# 06_-_MICRO_CONTROLLER_CONNECTORS.net
KiCad netlist of a schematic drawn in Altium Designer
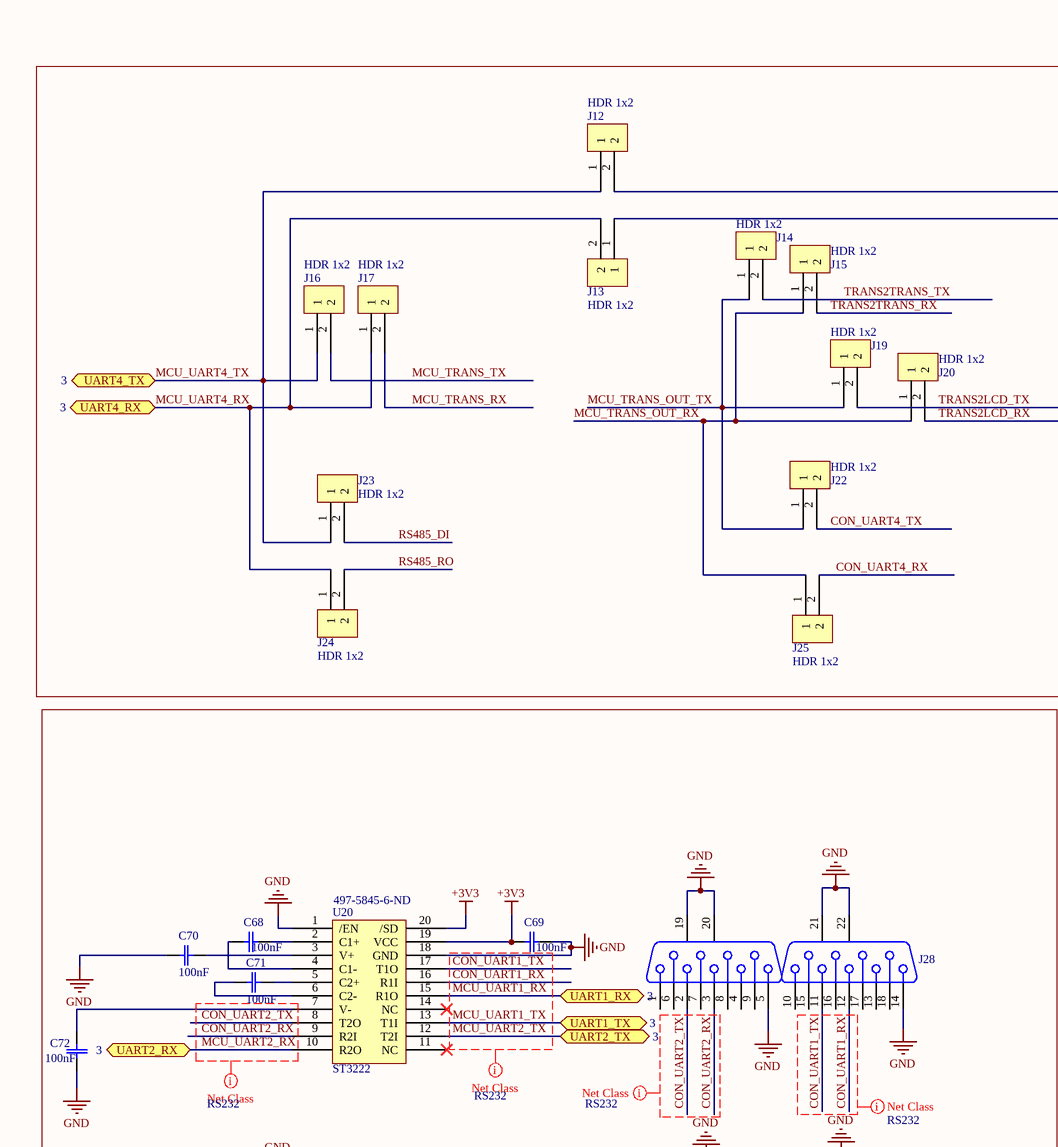
[diagram p0: [06] - MICRO CONTROLLER CONNECTORS.SchDoc, top left]
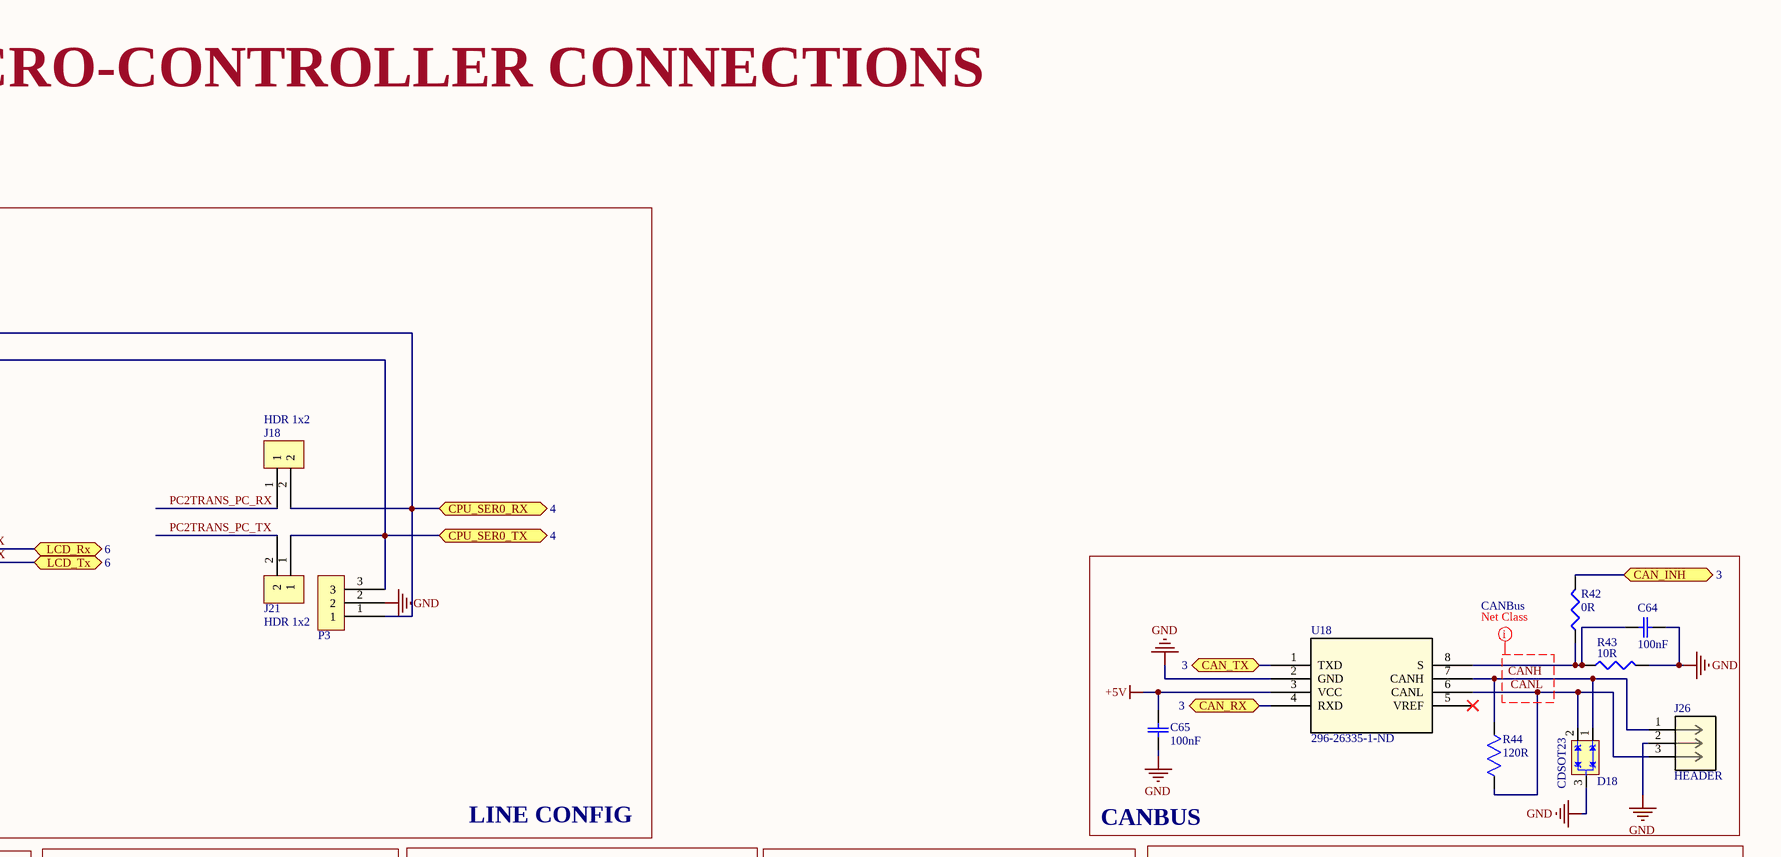
[diagram p1: [06] - MICRO CONTROLLER CONNECTORS.SchDoc, top right]
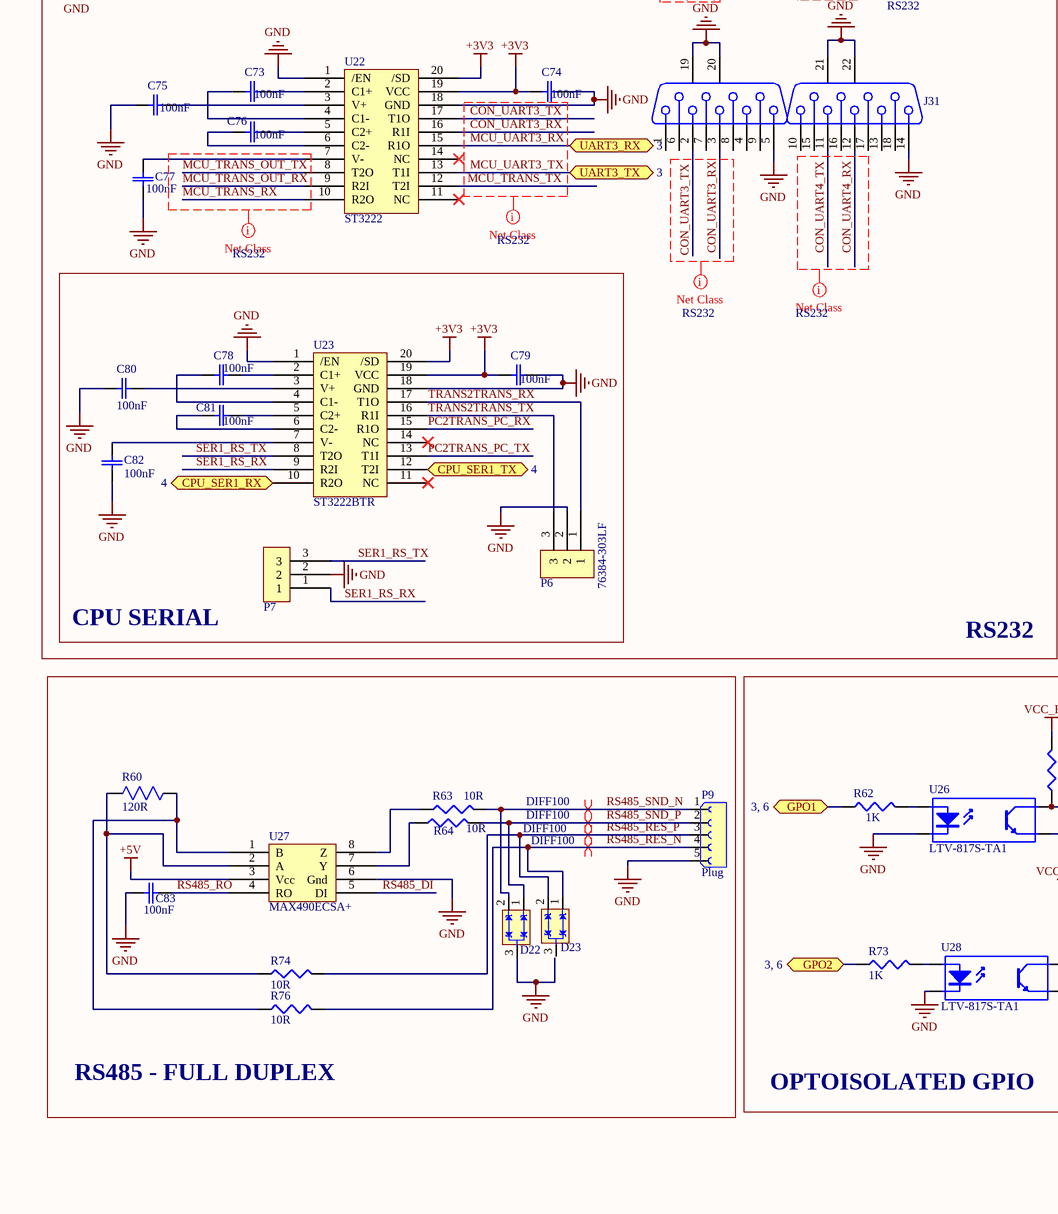
[diagram p2: [06] - MICRO CONTROLLER CONNECTORS.SchDoc, bottom left]
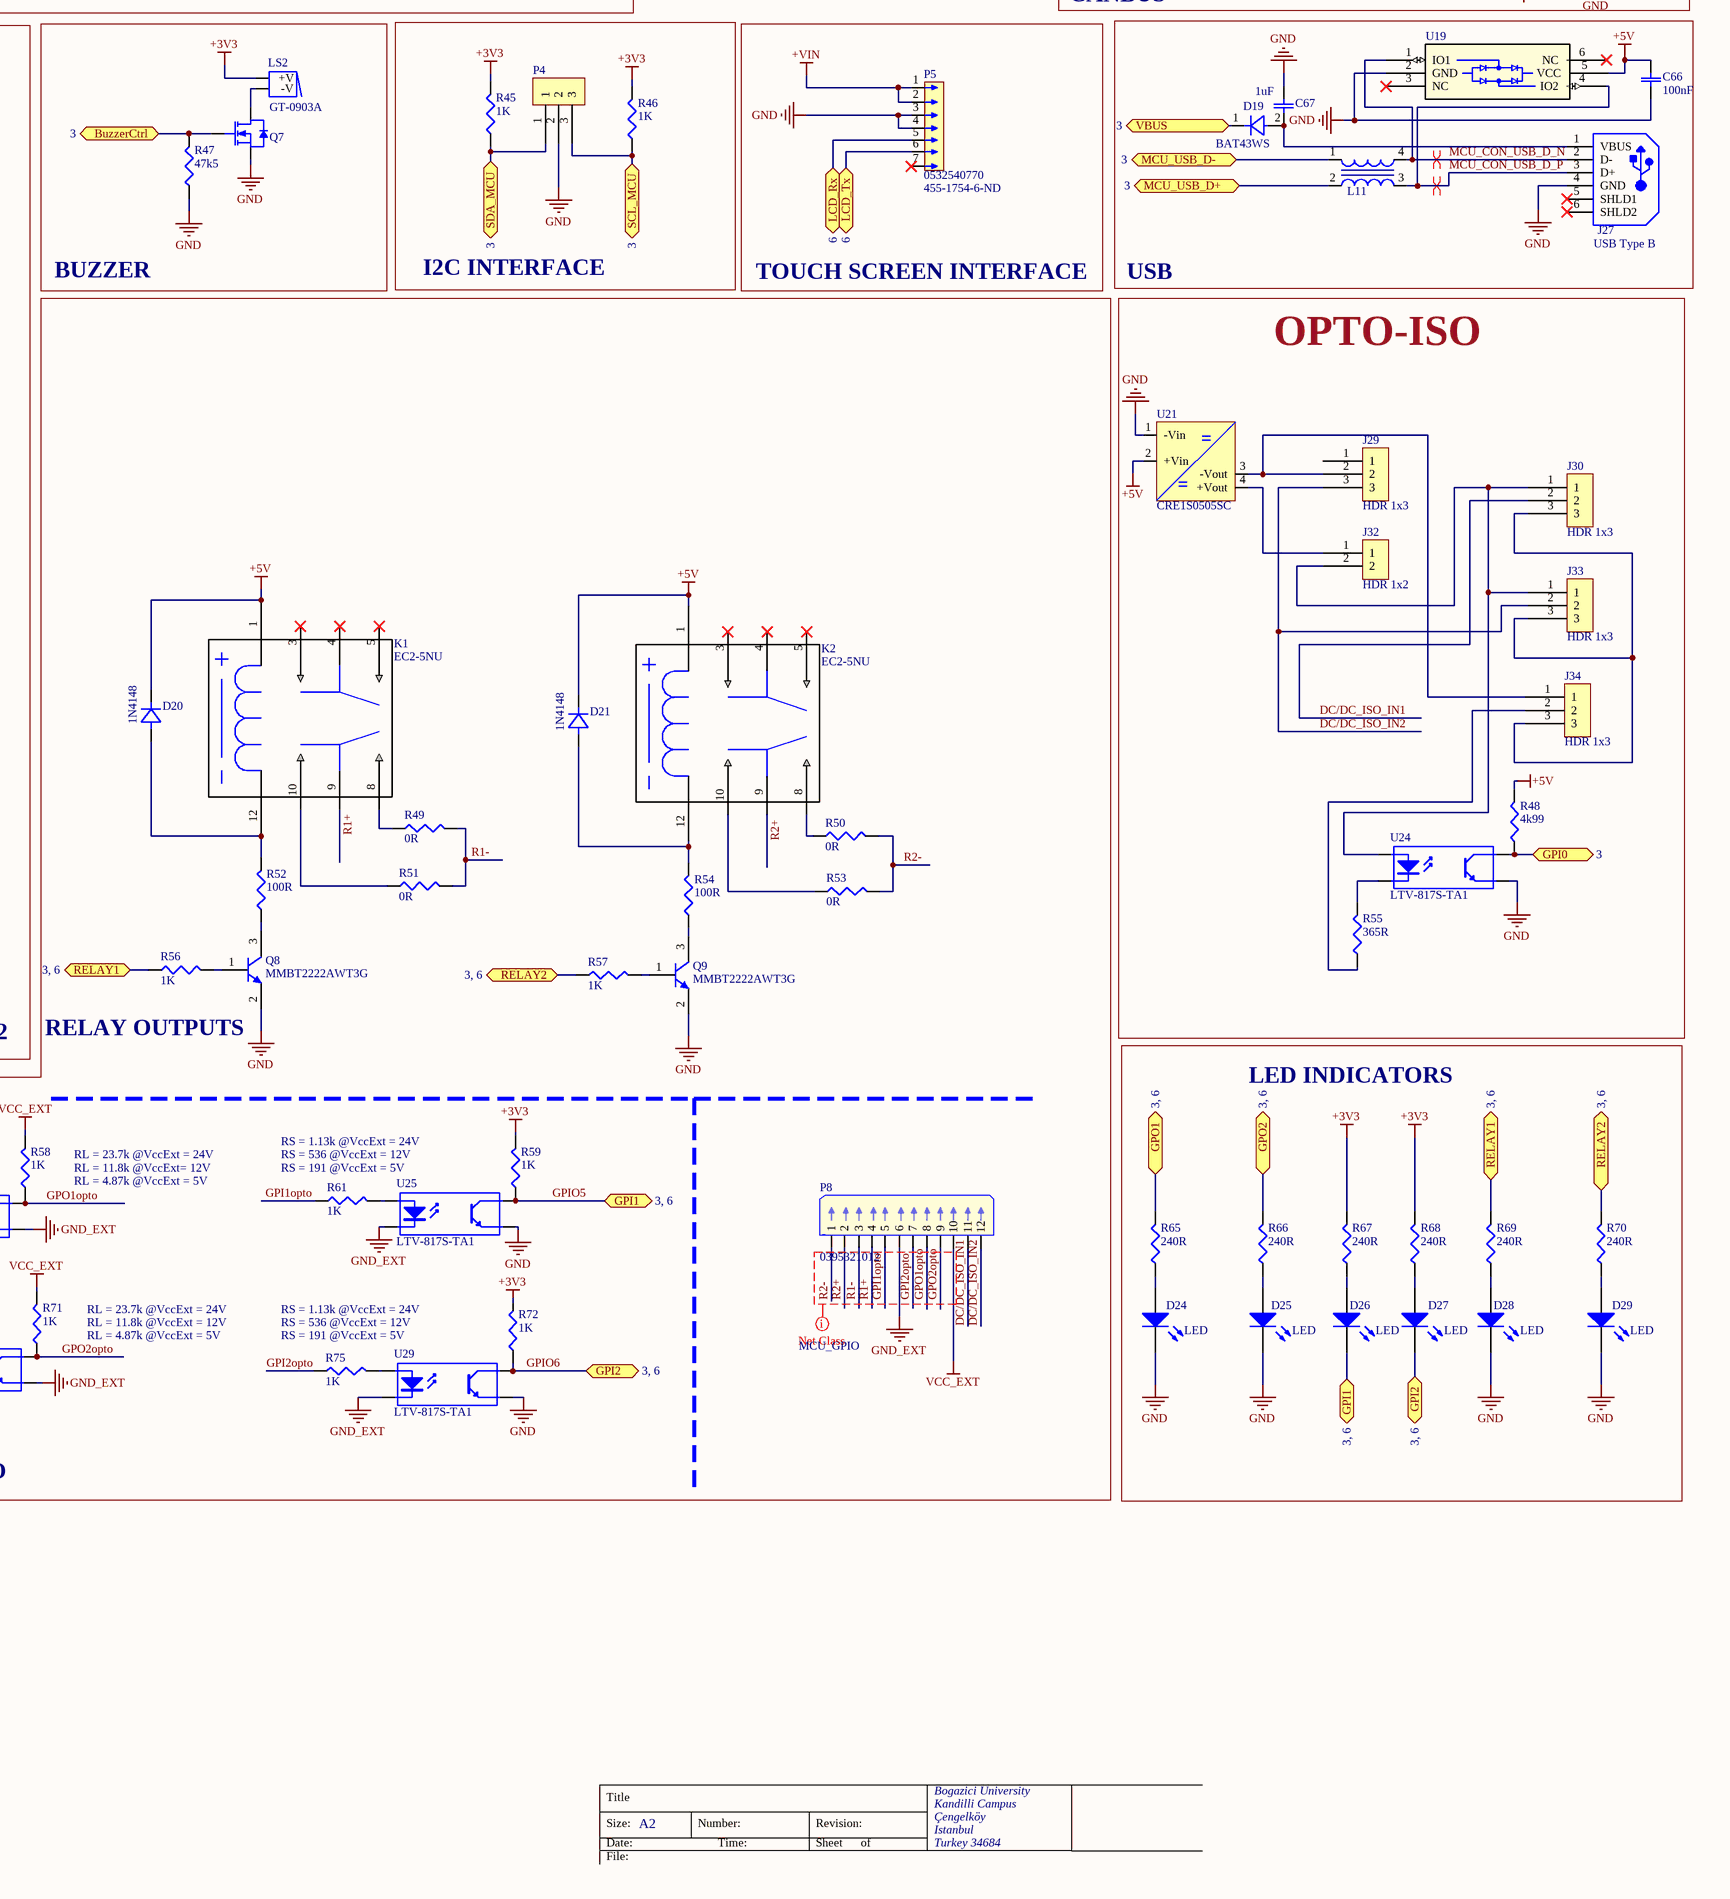
[diagram p3: [06] - MICRO CONTROLLER CONNECTORS.SchDoc, bottom right]

(export (version "E")
  (design (tool "Eeschema 10.0.6"))
  (components
    (comp (ref "C64")
      (value "100nF")
      (footprint "C0402")
      (description "CAP CER 0.1UF 25V X5R 0402")
      (fields (field (name "TOLERANCE") "±10%") (field (name ".CHECKED SCH") "CHK"))
      (libsource (lib "SYNCBOX_V3I1") (part "CL05A104KA5NNNC"))
    )
    (comp (ref "C65")
      (value "100nF")
      (footprint "C0402")
      (description "CAP CER 0.1UF 25V X5R 0402")
      (fields (field (name "TOLERANCE") "±10%"))
      (libsource (lib "SYNCBOX_V3I1") (part "CL05A104KA5NNNC"))
    )
    (comp (ref "C66")
      (value "100nF")
      (footprint "C0402")
      (description "CAP CER 0.1UF 25V X5R 0402")
      (fields (field (name "TOLERANCE") "±10%") (field (name ".CHECKED SCH") "CHK"))
      (libsource (lib "SYNCBOX_V3I1") (part "CL05A104KA5NNNC"))
    )
    (comp (ref "C67")
      (value "1uF")
      (footprint "CAP_3216")
      (description "CAP CER 1UF 50V X8R 1206")
      (fields
        (field (name "MANUFACTURER_PART_NUMBER") "CGA5L3X8R1H105K160AB")
        (field (name "TOLERANCE") "±10%")
        (field (name ".CHECKED SCH") "CHK")
      )
      (libsource (lib "SYNCBOX_V3I1") (part "CGA5L3X8R1H105K1"))
    )
    (comp (ref "C68")
      (value "100nF")
      (footprint "C0402")
      (description "CAP CER 0.1UF 25V X5R 0402")
      (fields (field (name "TOLERANCE") "±10%") (field (name ".CHECKED SCH") "CHK"))
      (libsource (lib "SYNCBOX_V3I1") (part "CL05A104KA5NNNC"))
    )
    (comp (ref "C69")
      (value "100nF")
      (footprint "C0402")
      (description "CAP CER 0.1UF 25V X5R 0402")
      (fields (field (name "TOLERANCE") "±10%") (field (name ".CHECKED SCH") "CHK"))
      (libsource (lib "SYNCBOX_V3I1") (part "CL05A104KA5NNNC"))
    )
    (comp (ref "C70")
      (value "100nF")
      (footprint "C0402")
      (description "CAP CER 0.1UF 25V X5R 0402")
      (fields (field (name "TOLERANCE") "±10%") (field (name ".CHECKED SCH") "CHK"))
      (libsource (lib "SYNCBOX_V3I1") (part "CL05A104KA5NNNC"))
    )
    (comp (ref "C71")
      (value "100nF")
      (footprint "C0402")
      (description "CAP CER 0.1UF 25V X5R 0402")
      (fields (field (name "TOLERANCE") "±10%") (field (name ".CHECKED SCH") "CHK"))
      (libsource (lib "SYNCBOX_V3I1") (part "CL05A104KA5NNNC"))
    )
    (comp (ref "C72")
      (value "100nF")
      (footprint "C0402")
      (description "CAP CER 0.1UF 25V X5R 0402")
      (fields (field (name "TOLERANCE") "±10%") (field (name ".CHECKED SCH") "CHK"))
      (libsource (lib "SYNCBOX_V3I1") (part "CL05A104KA5NNNC"))
    )
    (comp (ref "C73")
      (value "100nF")
      (footprint "C0402")
      (description "CAP CER 0.1UF 25V X5R 0402")
      (fields (field (name "TOLERANCE") "±10%") (field (name ".CHECKED SCH") "CHK"))
      (libsource (lib "SYNCBOX_V3I1") (part "CL05A104KA5NNNC"))
    )
    (comp (ref "C74")
      (value "100nF")
      (footprint "C0402")
      (description "CAP CER 0.1UF 25V X5R 0402")
      (fields (field (name "TOLERANCE") "±10%") (field (name ".CHECKED SCH") "CHK"))
      (libsource (lib "SYNCBOX_V3I1") (part "CL05A104KA5NNNC"))
    )
    (comp (ref "C75")
      (value "100nF")
      (footprint "C0402")
      (description "CAP CER 0.1UF 25V X5R 0402")
      (fields (field (name "TOLERANCE") "±10%") (field (name ".CHECKED SCH") "CHK"))
      (libsource (lib "SYNCBOX_V3I1") (part "CL05A104KA5NNNC"))
    )
    (comp (ref "C76")
      (value "100nF")
      (footprint "C0402")
      (description "CAP CER 0.1UF 25V X5R 0402")
      (fields (field (name "TOLERANCE") "±10%") (field (name ".CHECKED SCH") "CHK"))
      (libsource (lib "SYNCBOX_V3I1") (part "CL05A104KA5NNNC"))
    )
    (comp (ref "C77")
      (value "100nF")
      (footprint "C0402")
      (description "CAP CER 0.1UF 25V X5R 0402")
      (fields (field (name "TOLERANCE") "±10%") (field (name ".CHECKED SCH") "CHK"))
      (libsource (lib "SYNCBOX_V3I1") (part "CL05A104KA5NNNC"))
    )
    (comp (ref "C78")
      (value "100nF")
      (footprint "C0402")
      (description "CAP CER 0.1UF 25V X5R 0402")
      (fields (field (name "TOLERANCE") "±10%") (field (name ".CHECKED SCH") "CHK"))
      (libsource (lib "SYNCBOX_V3I1") (part "CL05A104KA5NNNC"))
    )
    (comp (ref "C79")
      (value "100nF")
      (footprint "C0402")
      (description "CAP CER 0.1UF 25V X5R 0402")
      (fields (field (name "TOLERANCE") "±10%") (field (name ".CHECKED SCH") "CHK"))
      (libsource (lib "SYNCBOX_V3I1") (part "CL05A104KA5NNNC"))
    )
    (comp (ref "C80")
      (value "100nF")
      (footprint "C0402")
      (description "CAP CER 0.1UF 25V X5R 0402")
      (fields (field (name "TOLERANCE") "±10%") (field (name ".CHECKED SCH") "CHK"))
      (libsource (lib "SYNCBOX_V3I1") (part "CL05A104KA5NNNC"))
    )
    (comp (ref "C81")
      (value "100nF")
      (footprint "C0402")
      (description "CAP CER 0.1UF 25V X5R 0402")
      (fields (field (name "TOLERANCE") "±10%") (field (name ".CHECKED SCH") "CHK"))
      (libsource (lib "SYNCBOX_V3I1") (part "CL05A104KA5NNNC"))
    )
    (comp (ref "C82")
      (value "100nF")
      (footprint "C0402")
      (description "CAP CER 0.1UF 25V X5R 0402")
      (fields (field (name "TOLERANCE") "±10%") (field (name ".CHECKED SCH") "CHK"))
      (libsource (lib "SYNCBOX_V3I1") (part "CL05A104KA5NNNC"))
    )
    (comp (ref "C83")
      (value "100nF")
      (footprint "C0402")
      (description "CAP CER 0.1UF 25V X5R 0402")
      (fields (field (name "TOLERANCE") "±10%"))
      (libsource (lib "SYNCBOX_V3I1") (part "CL05A104KA5NNNC"))
    )
    (comp (ref "D18")
      (value "CDSOT23")
      (footprint "SOT-23-3")
      (description "TVS DIODE 24V 40V SOT23")
      (fields (field (name ".CHECKED SCH") "CHK"))
      (libsource (lib "SYNCBOX_V3I1") (part "CDSOT23"))
    )
    (comp (ref "D19")
      (value "BAT43WS")
      (footprint "SOD323")
      (description "DIODE SCHOTTKY 30V 200MA SOD323")
      (fields (field (name ".CHECKED SCH") "CHK"))
      (libsource (lib "SYNCBOX_V3I1") (part "BAT43WS-7-F"))
    )
    (comp (ref "D20")
      (value "1N4148")
      (footprint "SOD123-L")
      (description "DIODE GEN PURP 100V 150MA SOD123")
      (fields
        (field (name "BASE PART NUMBER") "1N4148W")
        (field (name "COPYRIGHT") "Copyright (C) 2016 Accelerated Designs. All rights reserved")
        (field (name ".CHECKED SCH") "CHK")
      )
      (libsource (lib "SYNCBOX_V3I1") (part "1N4148"))
    )
    (comp (ref "D21")
      (value "1N4148")
      (footprint "SOD123-L")
      (description "DIODE GEN PURP 100V 150MA SOD123")
      (fields
        (field (name "BASE PART NUMBER") "1N4148W")
        (field (name "COPYRIGHT") "Copyright (C) 2016 Accelerated Designs. All rights reserved")
        (field (name ".CHECKED SCH") "CHK")
      )
      (libsource (lib "SYNCBOX_V3I1") (part "1N4148"))
    )
    (comp (ref "D22")
      (value "TVS")
      (footprint "SOT-23-3")
      (fields (field (name ".CHECKED SCH") "CHK") (field (name ".CHECKED PCB") "CHK"))
      (libsource (lib "SYNCBOX_V3I1") (part "CDSOT23-SM712"))
    )
    (comp (ref "D23")
      (value "TVS")
      (footprint "SOT-23-3")
      (libsource (lib "SYNCBOX_V3I1") (part "CDSOT23-SM712"))
    )
    (comp (ref "D24")
      (value "LED")
      (footprint "D0603_Directional")
      (description "LED COOL WHITE DIFFUSED 0603 SMD")
      (fields (field (name ".CHECKED SCH") "CHK"))
      (libsource (lib "SYNCBOX_V3I1") (part "LW Q38E-Q1OO-3K6L-1"))
    )
    (comp (ref "D25")
      (value "LED")
      (footprint "D0603_Directional")
      (description "LED COOL WHITE DIFFUSED 0603 SMD")
      (fields (field (name ".CHECKED SCH") "CHK"))
      (libsource (lib "SYNCBOX_V3I1") (part "LW Q38E-Q1OO-3K6L-1"))
    )
    (comp (ref "D26")
      (value "LED")
      (footprint "D0603_Directional")
      (description "LED COOL WHITE DIFFUSED 0603 SMD")
      (fields (field (name ".CHECKED SCH") "CHK"))
      (libsource (lib "SYNCBOX_V3I1") (part "LW Q38E-Q1OO-3K6L-1"))
    )
    (comp (ref "D27")
      (value "LED")
      (footprint "D0603_Directional")
      (description "LED RED DIFFUSED 0603 SMD")
      (fields (field (name "PUBLISHER") "Altium Limited") (field (name ".CHECKED SCH") "CHK"))
      (libsource (lib "SYNCBOX_V3I1") (part "LS Q976-NR-1"))
    )
    (comp (ref "D28")
      (value "LED")
      (footprint "D0603_Directional")
      (description "LED COOL WHITE DIFFUSED 0603 SMD")
      (fields (field (name ".CHECKED SCH") "CHK"))
      (libsource (lib "SYNCBOX_V3I1") (part "LW Q38E-Q1OO-3K6L-1"))
    )
    (comp (ref "D29")
      (value "LED")
      (footprint "D0603_Directional")
      (description "LED COOL WHITE DIFFUSED 0603 SMD")
      (fields (field (name ".CHECKED SCH") "CHK"))
      (libsource (lib "SYNCBOX_V3I1") (part "LW Q38E-Q1OO-3K6L-1"))
    )
    (comp (ref "J12")
      (value "HDR 1x2")
      (footprint "HDR_1x2_2.54MM")
      (description "BERGSTIK II .100\" SR STRAIGHT")
      (fields
        (field (name "MANUFACTURER") "FCI")
        (field (name "MANUFACTURER PART NUMBER") "68001-202HLF")
        (field (name ".CHECKED SCH") "CHK")
      )
      (libsource (lib "") (part "68001-202HLF_1"))
    )
    (comp (ref "J13")
      (value "HDR 1x2")
      (footprint "HDR_1x2_2.54MM")
      (description "BERGSTIK II .100\" SR STRAIGHT")
      (fields
        (field (name "MANUFACTURER") "FCI")
        (field (name "MANUFACTURER PART NUMBER") "68001-202HLF")
        (field (name ".CHECKED SCH") "CHK")
      )
      (libsource (lib "iMX6 Rex Development Baseboard V1I1") (part "68001-202HLF"))
    )
    (comp (ref "J14")
      (value "HDR 1x2")
      (footprint "HDR_1x2_2.54MM")
      (description "BERGSTIK II .100\" SR STRAIGHT")
      (fields
        (field (name "MANUFACTURER") "FCI")
        (field (name "MANUFACTURER PART NUMBER") "68001-202HLF")
        (field (name ".CHECKED SCH") "CHK")
      )
      (libsource (lib "") (part "68001-202HLF_1"))
    )
    (comp (ref "J15")
      (value "HDR 1x2")
      (footprint "HDR_1x2_2.54MM")
      (description "BERGSTIK II .100\" SR STRAIGHT")
      (fields
        (field (name "MANUFACTURER") "FCI")
        (field (name "MANUFACTURER PART NUMBER") "68001-202HLF")
        (field (name ".CHECKED SCH") "CHK")
      )
      (libsource (lib "") (part "68001-202HLF_1"))
    )
    (comp (ref "J16")
      (value "HDR 1x2")
      (footprint "HDR_1x2_2.54MM")
      (description "BERGSTIK II .100\" SR STRAIGHT")
      (fields
        (field (name "MANUFACTURER") "FCI")
        (field (name "MANUFACTURER PART NUMBER") "68001-202HLF")
        (field (name ".CHECKED SCH") "CHK")
      )
      (libsource (lib "") (part "68001-202HLF_1"))
    )
    (comp (ref "J17")
      (value "HDR 1x2")
      (footprint "HDR_1x2_2.54MM")
      (description "BERGSTIK II .100\" SR STRAIGHT")
      (fields
        (field (name "MANUFACTURER") "FCI")
        (field (name "MANUFACTURER PART NUMBER") "68001-202HLF")
        (field (name ".CHECKED SCH") "CHK")
      )
      (libsource (lib "") (part "68001-202HLF_1"))
    )
    (comp (ref "J18")
      (value "HDR 1x2")
      (footprint "HDR_1x2_2.54MM")
      (description "BERGSTIK II .100\" SR STRAIGHT")
      (fields (field (name "MANUFACTURER") "FCI") (field (name "MANUFACTURER PART NUMBER") "68001-202HLF"))
      (libsource (lib "") (part "68001-202HLF_1"))
    )
    (comp (ref "J19")
      (value "HDR 1x2")
      (footprint "HDR_1x2_2.54MM")
      (description "BERGSTIK II .100\" SR STRAIGHT")
      (fields
        (field (name "MANUFACTURER") "FCI")
        (field (name "MANUFACTURER PART NUMBER") "68001-202HLF")
        (field (name ".CHECKED SCH") "CHK")
      )
      (libsource (lib "") (part "68001-202HLF_1"))
    )
    (comp (ref "J20")
      (value "HDR 1x2")
      (footprint "HDR_1x2_2.54MM")
      (description "BERGSTIK II .100\" SR STRAIGHT")
      (fields
        (field (name "MANUFACTURER") "FCI")
        (field (name "MANUFACTURER PART NUMBER") "68001-202HLF")
        (field (name ".CHECKED SCH") "CHK")
      )
      (libsource (lib "") (part "68001-202HLF_1"))
    )
    (comp (ref "J21")
      (value "HDR 1x2")
      (footprint "HDR_1x2_2.54MM")
      (description "BERGSTIK II .100\" SR STRAIGHT")
      (fields (field (name "MANUFACTURER") "FCI") (field (name "MANUFACTURER PART NUMBER") "68001-202HLF"))
      (libsource (lib "iMX6 Rex Development Baseboard V1I1") (part "68001-202HLF"))
    )
    (comp (ref "J22")
      (value "HDR 1x2")
      (footprint "HDR_1x2_2.54MM")
      (description "BERGSTIK II .100\" SR STRAIGHT")
      (fields
        (field (name "MANUFACTURER") "FCI")
        (field (name "MANUFACTURER PART NUMBER") "68001-202HLF")
        (field (name ".CHECKED SCH") "CHK")
      )
      (libsource (lib "") (part "68001-202HLF_1"))
    )
    (comp (ref "J23")
      (value "HDR 1x2")
      (footprint "HDR_1x2_2.54MM")
      (description "BERGSTIK II .100\" SR STRAIGHT")
      (fields
        (field (name "MANUFACTURER") "FCI")
        (field (name "MANUFACTURER PART NUMBER") "68001-202HLF")
        (field (name ".CHECKED SCH") "CHK")
      )
      (libsource (lib "") (part "68001-202HLF_1"))
    )
    (comp (ref "J24")
      (value "HDR 1x2")
      (footprint "HDR_1x2_2.54MM")
      (description "BERGSTIK II .100\" SR STRAIGHT")
      (fields
        (field (name "MANUFACTURER") "FCI")
        (field (name "MANUFACTURER PART NUMBER") "68001-202HLF")
        (field (name ".CHECKED SCH") "CHK")
      )
      (libsource (lib "") (part "68001-202HLF_2"))
    )
    (comp (ref "J25")
      (value "HDR 1x2")
      (footprint "HDR_1x2_2.54MM")
      (description "BERGSTIK II .100\" SR STRAIGHT")
      (fields
        (field (name "MANUFACTURER") "FCI")
        (field (name "MANUFACTURER PART NUMBER") "68001-202HLF")
        (field (name ".CHECKED SCH") "CHK")
      )
      (libsource (lib "") (part "68001-202HLF_2"))
    )
    (comp (ref "J26")
      (value "HEADER")
      (footprint "TerminalBlock3P508")
      (description "TERM BLOCK HDR 3POS 90DEG 5MM")
      (fields (field (name "MANUFACTURER_PART_NUMBER") "796644-3"))
      (libsource (lib "SYNCBOX_V3I1") (part "796644-3"))
    )
    (comp (ref "J27")
      (value "USB Type B")
      (footprint "USB-B RECEPTACLE")
      (fields (field (name ".CHECKED SCH") "CHK"))
      (libsource (lib "TE Audio, Video and High Speed Serial Connectors") (part "292304-1"))
    )
    (comp (ref "J28")
      (value "DSUB-9 Stacked")
      (footprint "DSUB9-Double")
      (description "189-009-613R491")
      (fields (field (name "PUBLISHER") "Altium Limited") (field (name ".CHECKED SCH") "CHK"))
      (libsource (lib "SYNCBOX_V3I1") (part "DSUB-9 Stack"))
    )
    (comp (ref "J29")
      (value "HDR 1x3")
      (footprint "HDR_1X3_2.54MM")
      (description "BERGSTIK II .100\" SR STRAIGHT")
      (fields
        (field (name "MANUFACTURER") "FCI")
        (field (name "MANUFACTURER PART NUMBER") "68000-103HLF")
        (field (name ".CHECKED SCH") "CHK")
        (field (name ".CREATOR") "MM")
      )
      (libsource (lib "SYNCBOX_V3I1") (part "68000-103HLF"))
    )
    (comp (ref "J30")
      (value "HDR 1x3")
      (footprint "Hdr_1x3_2.54mm")
      (description "BERGSTIK II .100\" SR STRAIGHT")
      (fields
        (field (name "MANUFACTURER") "FCI")
        (field (name "MANUFACTURER PART NUMBER") "68000-103HLF")
        (field (name ".CREATOR") "MM")
        (field (name ".CHECKED SCH") "CHK")
      )
      (libsource (lib "iMX6 Rex Development Baseboard V1I1") (part "68000-103HLF"))
    )
    (comp (ref "J31")
      (value "DSUB-9 Stacked")
      (footprint "DSUB9-Double")
      (description "189-009-613R491")
      (fields (field (name "PUBLISHER") "Altium Limited") (field (name ".CHECKED SCH") "CHK"))
      (libsource (lib "SYNCBOX_V3I1") (part "DSUB-9 Stack"))
    )
    (comp (ref "J32")
      (value "HDR 1x2")
      (footprint "HDR_1x2_2.54MM")
      (description "BERGSTIK II .100\" SR STRAIGHT")
      (fields
        (field (name "MANUFACTURER") "FCI")
        (field (name "MANUFACTURER PART NUMBER") "68001-202HLF")
        (field (name ".CHECKED SCH") "CHK")
      )
      (libsource (lib "") (part "68001-202HLF_3"))
    )
    (comp (ref "J33")
      (value "HDR 1x3")
      (footprint "Hdr_1x3_2.54mm")
      (description "BERGSTIK II .100\" SR STRAIGHT")
      (fields
        (field (name "MANUFACTURER") "FCI")
        (field (name "MANUFACTURER PART NUMBER") "68000-103HLF")
        (field (name ".CREATOR") "MM")
        (field (name ".CHECKED SCH") "CHK")
      )
      (libsource (lib "iMX6 Rex Development Baseboard V1I1") (part "68000-103HLF"))
    )
    (comp (ref "J34")
      (value "HDR 1x3")
      (footprint "Hdr_1x3_2.54mm")
      (description "BERGSTIK II .100\" SR STRAIGHT")
      (fields
        (field (name "MANUFACTURER") "FCI")
        (field (name "MANUFACTURER PART NUMBER") "68000-103HLF")
        (field (name ".CREATOR") "MM")
        (field (name ".CHECKED SCH") "CHK")
      )
      (libsource (lib "iMX6 Rex Development Baseboard V1I1") (part "68000-103HLF"))
    )
    (comp (ref "K1")
      (value "EC2-5NU")
      (footprint "EC2NU")
      (description "RELAY GEN PURPOSE DPDT 2A 5V")
      (fields (field (name ".CHECKED SCH") "CHK"))
      (libsource (lib "SYNCBOX_V3I1") (part "EC2-5NU"))
    )
    (comp (ref "K2")
      (value "EC2-5NU")
      (footprint "EC2NU")
      (description "RELAY GEN PURPOSE DPDT 2A 5V")
      (libsource (lib "SYNCBOX_V3I1") (part "EC2-5NU"))
    )
    (comp (ref "L11")
      (value "ACM2012-900-2P-T002")
      (footprint "ACM2012")
      (description "CHOKE COMM MODE 90 OHM .4A SMD")
      (fields
        (field (name "MANUFACTURER") "TDK Corporation")
        (field (name "TOLERANCE") "±1%")
        (field (name ".CHECKED PCB") "CHK")
        (field (name ".CHECKED SCH") "CHK")
      )
      (libsource (lib "SYNCBOX_V3I1") (part "ACM2012-900-2P-T002"))
    )
    (comp (ref "LS2")
      (value "GT-0903A")
      (footprint "GT-0903A")
      (description "AUDIO MAGNETIC XDCR 2-4V TH")
      (fields (field (name ".CHECKED PCB") "CHK") (field (name ".CHECKED SCH") "CHK"))
      (libsource (lib "SYNCBOX_V3I1") (part "GT-0903A"))
    )
    (comp (ref "P3")
      (value "76384-303LF")
      (footprint "HDR_1x3_2.54MM_SHDR_V2")
      (description "CONN HEADER 3POS .100\" STR GOLD")
      (fields (field (name "MANUFACTURER") "FCI") (field (name ".CREATOR") "MM"))
      (libsource (lib "") (part "76384-303LF_1"))
    )
    (comp (ref "P4")
      (value "76384-303LF")
      (footprint "HDR_1x3_2.54MM_SHDR_V2")
      (description "CONN HEADER 3POS .100\" STR GOLD")
      (fields
        (field (name "MANUFACTURER") "FCI")
        (field (name ".CREATOR") "MM")
        (field (name ".CHECKED SCH") "CHK")
      )
      (libsource (lib "SYNCBOX_V3I1") (part "76384-303LF"))
    )
    (comp (ref "P5")
      (value "0532540770")
      (footprint "WM3412-ND")
      (description "HEADER 2MM WTB R/A SQ PIN 7CKT")
      (fields (field (name "SUPPLIER PART NUMBER 1") "455-1754-6-ND"))
      (libsource (lib "SYNCBOX_V3I1") (part "0532540770"))
    )
    (comp (ref "P6")
      (value "76384-303LF")
      (footprint "HDR_1X3_2.54MM_SHDR_V2")
      (description "CONN HEADER 3POS .100\" STR GOLD")
      (fields (field (name "MANUFACTURER") "FCI") (field (name ".CREATOR") "MM"))
      (libsource (lib "") (part "76384-303LF_2"))
    )
    (comp (ref "P7")
      (value "76384-303LF")
      (footprint "HDR_1x3_2.54MM_SHDR_V2")
      (description "CONN HEADER 3POS .100\" STR GOLD")
      (fields
        (field (name "MANUFACTURER") "FCI")
        (field (name ".CREATOR") "MM")
        (field (name ".CHECKED SCH") "CHK")
      )
      (libsource (lib "") (part "76384-303LF_1"))
    )
    (comp (ref "P8")
      (value "0395321012")
      (footprint "WM7852-ND")
      (description "TERM BLOCK HDR 12POS 5.08MM")
      (fields (field (name ".CHECKED SCH") "CHK"))
      (libsource (lib "SYNCBOX_V3I1") (part "0395321012"))
    )
    (comp (ref "P9")
      (value "Plug")
      (footprint "691313710005")
      (description "TERM BLOCK HDR 5POS 90DEG 5MM")
      (fields (field (name ".CHECKED SCH") "CHK"))
      (libsource (lib "SYNCBOX_V3I1") (part "691313710005"))
    )
    (comp (ref "Q7")
      (value "MOSFET N-CH 20V 1A SOT323")
      (footprint "SC70_SOT323")
      (fields (field (name "PUBLISHER") "Altium Limited") (field (name ".CHECKED SCH") "CHK"))
      (libsource (lib "SYNCBOX_V3I1") (part "DMG1012UW-7"))
    )
    (comp (ref "Q8")
      (value "MMBT2222AWT3G")
      (footprint "SC70_SOT323")
      (description "TRANS NPN 40V 0.6A SC70-3")
      (fields
        (field (name "BASE PART NUMBER") "MMBT2222A")
        (field (name ".CHECKED PCB") "CHK")
        (field (name ".CHECKED SCH") "CHK")
      )
      (libsource (lib "SYNCBOX_V3I1") (part "MMBT2222AWT3G"))
    )
    (comp (ref "Q9")
      (value "MMBT2222AWT3G")
      (footprint "SC70_SOT323")
      (description "TRANS NPN 40V 0.6A SC70-3")
      (fields (field (name "BASE PART NUMBER") "MMBT2222A") (field (name ".CHECKED SCH") "CHK"))
      (libsource (lib "SYNCBOX_V3I1") (part "MMBT2222AWT3G"))
    )
    (comp (ref "R42")
      (value "0R")
      (footprint "R0402")
      (description "RES SMD 0 OHM JUMPER 1/16W 0402")
      (fields (field (name "TOLERANCE") "Jumper") (field (name ".CHECKED SCH") "CHK"))
      (libsource (lib "SYNCBOX_V3I1") (part "RC1005J000CS"))
    )
    (comp (ref "R43")
      (value "10R")
      (footprint "R0402")
      (description "RES 10.0 OHM 1/16W 1% 0402 SMD")
      (fields
        (field (name "MANUFACTURER") "Yageo")
        (field (name "MANUFACTURER PART NUMBER") "RC0402FR-0710RL")
        (field (name ".CHECKED SCH") "CHK")
      )
      (libsource (lib "SYNCBOX_V3I1") (part "RC0402FR-0710RL"))
    )
    (comp (ref "R44")
      (value "120R")
      (footprint "RES_R1632")
      (description "RES SMD 120 OHM 3/4W 1206 WIDE")
      (fields (field (name "TOLERANCE") "±1%") (field (name ".CHECKED SCH") "CHK"))
      (libsource (lib "SYNCBOX_V3I1") (part "LTR18EZPF1200"))
    )
    (comp (ref "R45")
      (value "1K")
      (footprint "R0402")
      (description "RES SMD 1K OHM 1% 1/10W 0402")
      (fields (field (name "TOLERANCE") "±1%") (field (name ".CHECKED SCH") "CHK"))
      (libsource (lib "SYNCBOX_V3I1") (part "ERJ-2RKF1001X"))
    )
    (comp (ref "R46")
      (value "1K")
      (footprint "R0402")
      (description "RES SMD 1K OHM 1% 1/10W 0402")
      (fields (field (name "TOLERANCE") "±1%") (field (name ".CHECKED SCH") "CHK"))
      (libsource (lib "SYNCBOX_V3I1") (part "ERJ-2RKF1001X"))
    )
    (comp (ref "R47")
      (value "47k5")
      (footprint "R0402")
      (description "RES 47.5K OHM 1/16W 1% 0402 SMD")
      (fields
        (field (name "MANUFACTURER") "Yageo")
        (field (name "MANUFACTURER PART NUMBER") "RC0402FR-0747K5L")
        (field (name ".CHECKED SCH") "CHK")
      )
      (libsource (lib "SYNCBOX_V3I1") (part "RC0402FR-0747K5L"))
    )
    (comp (ref "R48")
      (value "4k99")
      (footprint "R0402")
      (description "RES TF 4.99K OHM 1% 1/16W 0402")
      (fields
        (field (name "MANUFACTURER") "Stackpole Electronics Inc")
        (field (name "MANUFACTURER PART NUMBER") "RMCF0402FT4K99")
        (field (name ".CHECKED SCH") "CHK")
      )
      (libsource (lib "SYNCBOX_V3I1") (part "RMCF0402FT4K99"))
    )
    (comp (ref "R49")
      (value "0R")
      (footprint "R0402")
      (description "RES SMD 0 OHM JUMPER 1/16W 0402")
      (fields (field (name "TOLERANCE") "Jumper") (field (name ".CHECKED SCH") "CHK"))
      (libsource (lib "SYNCBOX_V3I1") (part "RC1005J000CS"))
    )
    (comp (ref "R50")
      (value "0R")
      (footprint "R0402")
      (description "RES SMD 0 OHM JUMPER 1/16W 0402")
      (fields (field (name "TOLERANCE") "Jumper") (field (name ".CHECKED SCH") "CHK"))
      (libsource (lib "SYNCBOX_V3I1") (part "RC1005J000CS"))
    )
    (comp (ref "R51")
      (value "0R")
      (footprint "R0402")
      (description "RES SMD 0 OHM JUMPER 1/16W 0402")
      (fields (field (name "TOLERANCE") "Jumper") (field (name ".CHECKED SCH") "CHK"))
      (libsource (lib "SYNCBOX_V3I1") (part "RC1005J000CS"))
    )
    (comp (ref "R52")
      (value "100R")
      (footprint "R0402")
      (description "RES SMD 100 OHM 1% 1/16W 0402")
      (fields (field (name "TOLERANCE") "±1%") (field (name ".CHECKED SCH") "CHK"))
      (libsource (lib "SYNCBOX_V3I1") (part "RC1005F101CS"))
    )
    (comp (ref "R53")
      (value "0R")
      (footprint "R0402")
      (description "RES SMD 0 OHM JUMPER 1/16W 0402")
      (fields (field (name "TOLERANCE") "Jumper") (field (name ".CHECKED SCH") "CHK"))
      (libsource (lib "SYNCBOX_V3I1") (part "RC1005J000CS"))
    )
    (comp (ref "R54")
      (value "100R")
      (footprint "R0402")
      (description "RES SMD 100 OHM 1% 1/16W 0402")
      (fields (field (name "TOLERANCE") "±1%") (field (name ".CHECKED SCH") "CHK"))
      (libsource (lib "SYNCBOX_V3I1") (part "RC1005F101CS"))
    )
    (comp (ref "R55")
      (value "365R")
      (footprint "R0402")
      (description "RES TF 365 OHM 1% 1/16W 0402")
      (fields
        (field (name "MANUFACTURER") "Stackpole Electronics Inc")
        (field (name "MANUFACTURER PART NUMBER") "RMCF0402FT365R")
        (field (name ".CHECKED SCH") "CHK")
      )
      (libsource (lib "SYNCBOX_V3I1") (part "RMCF0402FT365R"))
    )
    (comp (ref "R56")
      (value "1K")
      (footprint "R0402")
      (description "RES SMD 1K OHM 1% 1/10W 0402")
      (fields (field (name "TOLERANCE") "±1%") (field (name ".CHECKED SCH") "CHK"))
      (libsource (lib "SYNCBOX_V3I1") (part "ERJ-2RKF1001X"))
    )
    (comp (ref "R57")
      (value "1K")
      (footprint "R0402")
      (description "RES SMD 1K OHM 1% 1/10W 0402")
      (fields (field (name "TOLERANCE") "±1%") (field (name ".CHECKED SCH") "CHK"))
      (libsource (lib "SYNCBOX_V3I1") (part "ERJ-2RKF1001X"))
    )
    (comp (ref "R58")
      (value "1K")
      (footprint "R0402")
      (description "RES SMD 1K OHM 1% 1/10W 0402")
      (fields (field (name "TOLERANCE") "±1%") (field (name ".CHECKED SCH") "CHK"))
      (libsource (lib "SYNCBOX_V3I1") (part "ERJ-2RKF1001X"))
    )
    (comp (ref "R59")
      (value "1K")
      (footprint "R0402")
      (description "RES SMD 1K OHM 1% 1/10W 0402")
      (fields (field (name "TOLERANCE") "±1%"))
      (libsource (lib "SYNCBOX_V3I1") (part "ERJ-2RKF1001X"))
    )
    (comp (ref "R60")
      (value "120R")
      (footprint "RES_R1632")
      (description "RES SMD 120 OHM 3/4W 1206 WIDE")
      (fields (field (name "TOLERANCE") "±1%") (field (name ".CHECKED SCH") "CHK"))
      (libsource (lib "SYNCBOX_V3I1") (part "LTR18EZPF1200"))
    )
    (comp (ref "R61")
      (value "1K")
      (footprint "R0402")
      (description "RES SMD 1K OHM 1% 1/10W 0402")
      (fields (field (name "TOLERANCE") "±1%"))
      (libsource (lib "SYNCBOX_V3I1") (part "ERJ-2RKF1001X"))
    )
    (comp (ref "R62")
      (value "1K")
      (footprint "R0402")
      (description "RES SMD 1K OHM 1% 1/10W 0402")
      (fields (field (name "TOLERANCE") "±1%"))
      (libsource (lib "SYNCBOX_V3I1") (part "ERJ-2RKF1001X"))
    )
    (comp (ref "R63")
      (value "10R")
      (footprint "R0402")
      (description "RES 10.0 OHM 1/16W 1% 0402 SMD")
      (fields
        (field (name "MANUFACTURER") "Yageo")
        (field (name "MANUFACTURER PART NUMBER") "RC0402FR-0710RL")
        (field (name ".CHECKED SCH") "CHK")
      )
      (libsource (lib "SYNCBOX_V3I1") (part "RC0402FR-0710RL"))
    )
    (comp (ref "R64")
      (value "10R")
      (footprint "R0402")
      (description "RES 10.0 OHM 1/16W 1% 0402 SMD")
      (fields
        (field (name "MANUFACTURER") "Yageo")
        (field (name "MANUFACTURER PART NUMBER") "RC0402FR-0710RL")
        (field (name ".CHECKED SCH") "CHK")
      )
      (libsource (lib "SYNCBOX_V3I1") (part "RC0402FR-0710RL"))
    )
    (comp (ref "R65")
      (value "240R")
      (footprint "R0402")
      (description "RES TF 240 OHM 1% 0.0625W 0402")
      (fields
        (field (name "MANUFACTURER") "Stackpole Electronics Inc")
        (field (name "MANUFACTURER PART NUMBER") "RMCF0402FT240R")
        (field (name ".CHECKED SCH") "CHK")
      )
      (libsource (lib "SYNCBOX_V3I1") (part "RMCF0402FT240R"))
    )
    (comp (ref "R66")
      (value "240R")
      (footprint "R0402")
      (description "RES TF 240 OHM 1% 0.0625W 0402")
      (fields
        (field (name "MANUFACTURER") "Stackpole Electronics Inc")
        (field (name "MANUFACTURER PART NUMBER") "RMCF0402FT240R")
        (field (name ".CHECKED SCH") "CHK")
      )
      (libsource (lib "SYNCBOX_V3I1") (part "RMCF0402FT240R"))
    )
    (comp (ref "R67")
      (value "240R")
      (footprint "R0402")
      (description "RES TF 240 OHM 1% 0.0625W 0402")
      (fields
        (field (name "MANUFACTURER") "Stackpole Electronics Inc")
        (field (name "MANUFACTURER PART NUMBER") "RMCF0402FT240R")
        (field (name ".CHECKED SCH") "CHK")
      )
      (libsource (lib "SYNCBOX_V3I1") (part "RMCF0402FT240R"))
    )
    (comp (ref "R68")
      (value "240R")
      (footprint "R0402")
      (description "RES TF 240 OHM 1% 0.0625W 0402")
      (fields
        (field (name "MANUFACTURER") "Stackpole Electronics Inc")
        (field (name "MANUFACTURER PART NUMBER") "RMCF0402FT240R")
        (field (name ".CHECKED SCH") "CHK")
      )
      (libsource (lib "SYNCBOX_V3I1") (part "RMCF0402FT240R"))
    )
    (comp (ref "R69")
      (value "240R")
      (footprint "R0402")
      (description "RES TF 240 OHM 1% 0.0625W 0402")
      (fields
        (field (name "MANUFACTURER") "Stackpole Electronics Inc")
        (field (name "MANUFACTURER PART NUMBER") "RMCF0402FT240R")
        (field (name ".CHECKED SCH") "CHK")
      )
      (libsource (lib "SYNCBOX_V3I1") (part "RMCF0402FT240R"))
    )
    (comp (ref "R70")
      (value "240R")
      (footprint "R0402")
      (description "RES TF 240 OHM 1% 0.0625W 0402")
      (fields
        (field (name "MANUFACTURER") "Stackpole Electronics Inc")
        (field (name "MANUFACTURER PART NUMBER") "RMCF0402FT240R")
        (field (name ".CHECKED SCH") "CHK")
      )
      (libsource (lib "SYNCBOX_V3I1") (part "RMCF0402FT240R"))
    )
    (comp (ref "R71")
      (value "1K")
      (footprint "R0402")
      (description "RES SMD 1K OHM 1% 1/10W 0402")
      (fields (field (name "TOLERANCE") "±1%"))
      (libsource (lib "SYNCBOX_V3I1") (part "ERJ-2RKF1001X"))
    )
    (comp (ref "R72")
      (value "1K")
      (footprint "R0402")
      (description "RES SMD 1K OHM 1% 1/10W 0402")
      (fields (field (name "TOLERANCE") "±1%"))
      (libsource (lib "SYNCBOX_V3I1") (part "ERJ-2RKF1001X"))
    )
    (comp (ref "R73")
      (value "1K")
      (footprint "R0402")
      (description "RES SMD 1K OHM 1% 1/10W 0402")
      (fields (field (name "TOLERANCE") "±1%"))
      (libsource (lib "SYNCBOX_V3I1") (part "ERJ-2RKF1001X"))
    )
    (comp (ref "R74")
      (value "10R")
      (footprint "R0402")
      (description "RES 10.0 OHM 1/16W 1% 0402 SMD")
      (fields
        (field (name "MANUFACTURER") "Yageo")
        (field (name "MANUFACTURER PART NUMBER") "RC0402FR-0710RL")
        (field (name ".CHECKED SCH") "CHK")
      )
      (libsource (lib "SYNCBOX_V3I1") (part "RC0402FR-0710RL"))
    )
    (comp (ref "R75")
      (value "1K")
      (footprint "R0402")
      (description "RES SMD 1K OHM 1% 1/10W 0402")
      (fields (field (name "TOLERANCE") "±1%"))
      (libsource (lib "SYNCBOX_V3I1") (part "ERJ-2RKF1001X"))
    )
    (comp (ref "R76")
      (value "10R")
      (footprint "R0402")
      (description "RES 10.0 OHM 1/16W 1% 0402 SMD")
      (fields
        (field (name "MANUFACTURER") "Yageo")
        (field (name "MANUFACTURER PART NUMBER") "RC0402FR-0710RL")
        (field (name ".CHECKED SCH") "CHK")
      )
      (libsource (lib "SYNCBOX_V3I1") (part "RC0402FR-0710RL"))
    )
    (comp (ref "U18")
      (value "296-26335-1-ND")
      (footprint "D8")
      (description "IC EMC CAN TRANSCEIVER 8-SOIC")
      (fields
        (field (name "MANUFACTURER") "Texas Instruments")
        (field (name "MANUFACTURER_PART_NUMBER") "SN65HVD1050DR")
        (field (name ".CHECKED SCH") "CHK")
      )
      (libsource (lib "SYNCBOX_V3I1") (part "SN65HVD1050DR"))
    )
    (comp (ref "U19")
      (value "TVS DIODE 5V 8.1V SOT23-6")
      (footprint "21-0058I")
      (description "MAX3207E")
      (fields (field (name "MANUFACTURER_PART_NUMBER") "MAX3207EAUT+T") (field (name ".CHECKED SCH") "CHK"))
      (libsource (lib "SYNCBOX_V3I1") (part "MAX3207EAUT+T"))
    )
    (comp (ref "U20")
      (value "ST3222")
      (footprint "TSSOP20")
      (description "ST Dual RS232 Transceiver")
      (fields (field (name "SUPPLIER PART NUMBER 1") "497-5845-6-ND") (field (name ".CHECKED SCH") "CHK"))
      (libsource (lib "SYNCBOX_V3I1_gny") (part "ST3222"))
    )
    (comp (ref "U21")
      (value "CRE1S0505SC")
      (footprint "CRE1S0505SC")
      (description "DC/DC TH 1W 5-5V SIP SINGLE")
      (fields (field (name ".CHECKED SCH") "CHK"))
      (libsource (lib "SYNCBOX_V3I1") (part "CRE1S0505SC"))
    )
    (comp (ref "U22")
      (value "ST3222")
      (footprint "TSSOP20")
      (description "ST Dual RS232 Transceiver")
      (fields
        (field (name "MANUFACTURER") "STMicroelectronics")
        (field (name "MANUFACTURER PART NUMBER") "ST3222BTR")
        (field (name ".CHECKED SCH") "CHK")
      )
      (libsource (lib "SYNCBOX_V3I1") (part "ST3222"))
    )
    (comp (ref "U23")
      (value "ST3222BTR")
      (footprint "TSSOP20")
      (description "ST Dual RS232 Transceiver")
      (fields
        (field (name "MANUFACTURER") "STMicroelectronics")
        (field (name "BASE PART NUMBER") "ST3222")
        (field (name ".CHECKED SCH") "CHK")
      )
      (libsource (lib "SYNCBOX_V3I1") (part "ST3222"))
    )
    (comp (ref "U24")
      (value "LTV-817S-TA1")
      (footprint "4-SMD-opto")
      (description "OPTOISOLATR 5KV TRANSISTOR 4-SMD")
      (fields (field (name ".CHECKED SCH") "CHK"))
      (libsource (lib "SYNCBOX_V3I1") (part "LTV-817S-TA1"))
    )
    (comp (ref "U25")
      (value "LTV-817S-TA1")
      (footprint "4-SMD-opto")
      (description "OPTOISOLATR 5KV TRANSISTOR 4-SMD")
      (fields (field (name ".CHECKED SCH") "CHK"))
      (libsource (lib "SYNCBOX_V3I1") (part "LTV-817S-TA1"))
    )
    (comp (ref "U26")
      (value "LTV-817S-TA1")
      (footprint "4-SMD-opto")
      (description "OPTOISOLATR 5KV TRANSISTOR 4-SMD")
      (fields (field (name ".CHECKED SCH") "CHK"))
      (libsource (lib "SYNCBOX_V3I1") (part "LTV-817S-TA1"))
    )
    (comp (ref "U27")
      (value "MAX490ECSA+")
      (footprint "21-0041B_8")
      (description "IC TXRX RS485/RS422 8-SOIC")
      (fields (field (name ".CHECKED SCH") "CHK"))
      (libsource (lib "SYNCBOX_V3I1") (part "MAX490"))
    )
    (comp (ref "U28")
      (value "LTV-817S-TA1")
      (footprint "4-SMD-opto")
      (description "OPTOISOLATR 5KV TRANSISTOR 4-SMD")
      (fields (field (name ".CHECKED SCH") "CHK"))
      (libsource (lib "SYNCBOX_V3I1") (part "LTV-817S-TA1"))
    )
    (comp (ref "U29")
      (value "LTV-817S-TA1")
      (footprint "4-SMD-opto")
      (description "OPTOISOLATR 5KV TRANSISTOR 4-SMD")
      (fields (field (name ".CHECKED SCH") "CHK"))
      (libsource (lib "SYNCBOX_V3I1") (part "LTV-817S-TA1"))
    )
  )
  (nets
    (net (code "1") (name "+3V3") (class "Default")
      (node (ref "C69") (pin "1") (pinfunction "1_1") (pintype "passive"))
      (node (ref "C74") (pin "2") (pinfunction "2_2") (pintype "passive"))
      (node (ref "C79") (pin "2") (pinfunction "2_2") (pintype "passive"))
      (node (ref "LS2") (pin "1") (pinfunction "+V_1") (pintype "passive"))
      (node (ref "R45") (pin "2") (pinfunction "2_2") (pintype "passive"))
      (node (ref "R46") (pin "2") (pinfunction "2_2") (pintype "passive"))
      (node (ref "R59") (pin "2") (pinfunction "2_2") (pintype "passive"))
      (node (ref "R67") (pin "2") (pinfunction "2_2") (pintype "passive"))
      (node (ref "R68") (pin "2") (pinfunction "2_2") (pintype "passive"))
      (node (ref "R72") (pin "2") (pinfunction "2_2") (pintype "passive"))
      (node (ref "U20") (pin "19") (pinfunction "VCC_19") (pintype "passive"))
      (node (ref "U20") (pin "20") (pinfunction "/SD_20") (pintype "passive"))
      (node (ref "U22") (pin "19") (pinfunction "VCC_19") (pintype "passive"))
      (node (ref "U22") (pin "20") (pinfunction "/SD_20") (pintype "passive"))
      (node (ref "U23") (pin "19") (pinfunction "VCC_19") (pintype "passive"))
      (node (ref "U23") (pin "20") (pinfunction "/SD_20") (pintype "passive"))
    )
    (net (code "2") (name "+5V") (class "Default")
      (node (ref "C65") (pin "2") (pinfunction "2_2") (pintype "passive"))
      (node (ref "C66") (pin "2") (pinfunction "2_2") (pintype "passive"))
      (node (ref "D20") (pin "1") (pinfunction "1_1") (pintype "passive"))
      (node (ref "D21") (pin "1") (pinfunction "1_1") (pintype "passive"))
      (node (ref "K1") (pin "1") (pinfunction "1_1") (pintype "passive"))
      (node (ref "K2") (pin "1") (pinfunction "1_1") (pintype "passive"))
      (node (ref "R48") (pin "2") (pinfunction "2_2") (pintype "passive"))
      (node (ref "U18") (pin "3") (pinfunction "VCC_3") (pintype "power_in"))
      (node (ref "U19") (pin "5") (pinfunction "VCC_5") (pintype "power_in"))
      (node (ref "U21") (pin "2") (pinfunction "+Vin_2") (pintype "passive"))
      (node (ref "U27") (pin "3") (pinfunction "Vcc_3") (pintype "passive"))
    )
    (net (code "3") (name "+VIN") (class "Default")
      (node (ref "P5") (pin "1") (pinfunction "1_1") (pintype "passive"))
      (node (ref "P5") (pin "2") (pinfunction "2_2") (pintype "passive"))
    )
    (net (code "4") (name "/BuzzerCtrl") (class "Default")
      (node (ref "Q7") (pin "1") (pinfunction "G_1") (pintype "passive"))
      (node (ref "R47") (pin "2") (pinfunction "2_2") (pintype "passive"))
    )
    (net (code "5") (name "/CANH") (class "Default")
      (node (ref "D18") (pin "1") (pinfunction "1_1") (pintype "passive"))
      (node (ref "J26") (pin "1") (pinfunction "1_1") (pintype "passive"))
      (node (ref "R44") (pin "2") (pinfunction "2_2") (pintype "passive"))
      (node (ref "U18") (pin "7") (pinfunction "CANH_7") (pintype "passive"))
    )
    (net (code "6") (name "/CANL") (class "Default")
      (node (ref "D18") (pin "2") (pinfunction "2_2") (pintype "passive"))
      (node (ref "J26") (pin "3") (pinfunction "3_3") (pintype "passive"))
      (node (ref "R44") (pin "1") (pinfunction "1_1") (pintype "passive"))
      (node (ref "U18") (pin "6") (pinfunction "CANL_6") (pintype "passive"))
    )
    (net (code "7") (name "/CAN_INH") (class "Default")
      (node (ref "R42") (pin "2") (pinfunction "2_2") (pintype "passive"))
    )
    (net (code "8") (name "/CAN_RX") (class "Default")
      (node (ref "U18") (pin "4") (pinfunction "RXD_4") (pintype "passive"))
    )
    (net (code "9") (name "/CAN_TX") (class "Default")
      (node (ref "U18") (pin "1") (pinfunction "TXD_1") (pintype "passive"))
    )
    (net (code "10") (name "/CON_UART1_RX") (class "Default")
      (node (ref "J28") (pin "12") (pinfunction "12_12") (pintype "passive"))
      (node (ref "U20") (pin "16") (pinfunction "R1I_16") (pintype "passive"))
    )
    (net (code "11") (name "/CON_UART1_TX") (class "Default")
      (node (ref "J28") (pin "11") (pinfunction "11_11") (pintype "passive"))
      (node (ref "U20") (pin "17") (pinfunction "T1O_17") (pintype "passive"))
    )
    (net (code "12") (name "/CON_UART2_RX") (class "Default")
      (node (ref "J28") (pin "3") (pinfunction "3_3") (pintype "passive"))
      (node (ref "U20") (pin "9") (pinfunction "R2I_9") (pintype "passive"))
    )
    (net (code "13") (name "/CON_UART2_TX") (class "Default")
      (node (ref "J28") (pin "2") (pinfunction "2_2") (pintype "passive"))
      (node (ref "U20") (pin "8") (pinfunction "T2O_8") (pintype "passive"))
    )
    (net (code "14") (name "/CON_UART3_RX") (class "Default")
      (node (ref "J31") (pin "3") (pinfunction "3_3") (pintype "passive"))
      (node (ref "U22") (pin "16") (pinfunction "R1I_16") (pintype "passive"))
    )
    (net (code "15") (name "/CON_UART3_TX") (class "Default")
      (node (ref "J31") (pin "2") (pinfunction "2_2") (pintype "passive"))
      (node (ref "U22") (pin "17") (pinfunction "T1O_17") (pintype "passive"))
    )
    (net (code "16") (name "/CON_UART4_RX") (class "Default")
      (node (ref "J25") (pin "2") (pinfunction "2_2") (pintype "passive"))
      (node (ref "J31") (pin "12") (pinfunction "12_12") (pintype "passive"))
    )
    (net (code "17") (name "/CON_UART4_TX") (class "Default")
      (node (ref "J22") (pin "2") (pinfunction "2_2") (pintype "passive"))
      (node (ref "J31") (pin "11") (pinfunction "11_11") (pintype "passive"))
    )
    (net (code "18") (name "/CPU_SER0_RX") (class "Default")
      (node (ref "J12") (pin "2") (pinfunction "2_2") (pintype "passive"))
      (node (ref "J18") (pin "2") (pinfunction "2_2") (pintype "passive"))
      (node (ref "P3") (pin "1") (pinfunction "1_1") (pintype "passive"))
    )
    (net (code "19") (name "/CPU_SER0_TX") (class "Default")
      (node (ref "J13") (pin "1") (pinfunction "1_1") (pintype "passive"))
      (node (ref "J21") (pin "1") (pinfunction "1_1") (pintype "passive"))
      (node (ref "P3") (pin "3") (pinfunction "3_3") (pintype "passive"))
    )
    (net (code "20") (name "/CPU_SER1_RX") (class "Default")
      (node (ref "U23") (pin "10") (pinfunction "R2O_10") (pintype "passive"))
    )
    (net (code "21") (name "/CPU_SER1_TX") (class "Default")
      (node (ref "U23") (pin "12") (pinfunction "T2I_12") (pintype "passive"))
    )
    (net (code "22") (name "/DC{slash}DC_ISO_IN1") (class "Default")
      (node (ref "J30") (pin "2") (pinfunction "2_2") (pintype "passive"))
      (node (ref "P8") (pin "11") (pinfunction "11_11") (pintype "passive"))
    )
    (net (code "23") (name "/DC{slash}DC_ISO_IN2") (class "Default")
      (node (ref "J29") (pin "3") (pinfunction "3_3") (pintype "passive"))
      (node (ref "J33") (pin "2") (pinfunction "2_2") (pintype "passive"))
      (node (ref "P8") (pin "12") (pinfunction "12_12") (pintype "passive"))
    )
    (net (code "24") (name "/GPI0") (class "Default")
      (node (ref "R48") (pin "1") (pinfunction "1_1") (pintype "passive"))
      (node (ref "U24") (pin "4") (pinfunction "C_4") (pintype "passive"))
    )
    (net (code "25") (name "/GPI1opto") (class "Default")
      (node (ref "P8") (pin "5") (pinfunction "5_5") (pintype "passive"))
      (node (ref "R61") (pin "1") (pinfunction "1_1") (pintype "passive"))
    )
    (net (code "26") (name "/GPI2opto") (class "Default")
      (node (ref "P8") (pin "7") (pinfunction "7_7") (pintype "passive"))
      (node (ref "R75") (pin "1") (pinfunction "1_1") (pintype "passive"))
    )
    (net (code "27") (name "/GPIO5") (class "Default")
      (node (ref "D26") (pin "2") (pinfunction "K_2") (pintype "passive"))
      (node (ref "R59") (pin "1") (pinfunction "1_1") (pintype "passive"))
      (node (ref "U25") (pin "4") (pinfunction "C_4") (pintype "passive"))
    )
    (net (code "28") (name "/GPIO6") (class "Default")
      (node (ref "D27") (pin "2") (pinfunction "K_2") (pintype "passive"))
      (node (ref "R72") (pin "1") (pinfunction "1_1") (pintype "passive"))
      (node (ref "U29") (pin "4") (pinfunction "C_4") (pintype "passive"))
    )
    (net (code "29") (name "/GPO1") (class "Default")
      (node (ref "R62") (pin "1") (pinfunction "1_1") (pintype "passive"))
      (node (ref "R65") (pin "2") (pinfunction "2_2") (pintype "passive"))
    )
    (net (code "30") (name "/GPO1opto") (class "Default")
      (node (ref "P8") (pin "8") (pinfunction "8_8") (pintype "passive"))
      (node (ref "R58") (pin "1") (pinfunction "1_1") (pintype "passive"))
      (node (ref "U26") (pin "4") (pinfunction "C_4") (pintype "passive"))
    )
    (net (code "31") (name "/GPO2") (class "Default")
      (node (ref "R66") (pin "2") (pinfunction "2_2") (pintype "passive"))
      (node (ref "R73") (pin "1") (pinfunction "1_1") (pintype "passive"))
    )
    (net (code "32") (name "/GPO2opto") (class "Default")
      (node (ref "P8") (pin "9") (pinfunction "9_9") (pintype "passive"))
      (node (ref "R71") (pin "1") (pinfunction "1_1") (pintype "passive"))
      (node (ref "U28") (pin "4") (pinfunction "C_4") (pintype "passive"))
    )
    (net (code "33") (name "/MCU_CON_USB_D_N") (class "Default")
      (node (ref "J27") (pin "2") (pinfunction "D-_2") (pintype "passive"))
      (node (ref "L11") (pin "4") (pinfunction "4_4") (pintype "passive"))
      (node (ref "U19") (pin "1") (pinfunction "IO1_1") (pintype "bidirectional"))
    )
    (net (code "34") (name "/MCU_CON_USB_D_P") (class "Default")
      (node (ref "J27") (pin "3") (pinfunction "D+_3") (pintype "passive"))
      (node (ref "L11") (pin "3") (pinfunction "3_3") (pintype "passive"))
      (node (ref "U19") (pin "4") (pinfunction "IO2_4") (pintype "bidirectional"))
    )
    (net (code "35") (name "/MCU_TRANS_OUT_RX") (class "Default")
      (node (ref "J15") (pin "1") (pinfunction "1_1") (pintype "passive"))
      (node (ref "J20") (pin "1") (pinfunction "1_1") (pintype "passive"))
      (node (ref "J25") (pin "1") (pinfunction "1_1") (pintype "passive"))
      (node (ref "U22") (pin "9") (pinfunction "R2I_9") (pintype "passive"))
    )
    (net (code "36") (name "/MCU_TRANS_OUT_TX") (class "Default")
      (node (ref "J14") (pin "1") (pinfunction "1_1") (pintype "passive"))
      (node (ref "J19") (pin "1") (pinfunction "1_1") (pintype "passive"))
      (node (ref "J22") (pin "1") (pinfunction "1_1") (pintype "passive"))
      (node (ref "U22") (pin "8") (pinfunction "T2O_8") (pintype "passive"))
    )
    (net (code "37") (name "/MCU_TRANS_RX") (class "Default")
      (node (ref "J17") (pin "2") (pinfunction "2_2") (pintype "passive"))
      (node (ref "U22") (pin "10") (pinfunction "R2O_10") (pintype "passive"))
    )
    (net (code "38") (name "/MCU_TRANS_TX") (class "Default")
      (node (ref "J16") (pin "2") (pinfunction "2_2") (pintype "passive"))
      (node (ref "U22") (pin "12") (pinfunction "T2I_12") (pintype "passive"))
    )
    (net (code "39") (name "/MCU_UART1_RX") (class "Default")
      (node (ref "U20") (pin "15") (pinfunction "R1O_15") (pintype "passive"))
    )
    (net (code "40") (name "/MCU_UART1_TX") (class "Default")
      (node (ref "U20") (pin "13") (pinfunction "T1I_13") (pintype "passive"))
    )
    (net (code "41") (name "/MCU_UART2_RX") (class "Default")
      (node (ref "U20") (pin "10") (pinfunction "R2O_10") (pintype "passive"))
    )
    (net (code "42") (name "/MCU_UART2_TX") (class "Default")
      (node (ref "U20") (pin "12") (pinfunction "T2I_12") (pintype "passive"))
    )
    (net (code "43") (name "/MCU_UART3_RX") (class "Default")
      (node (ref "U22") (pin "15") (pinfunction "R1O_15") (pintype "passive"))
    )
    (net (code "44") (name "/MCU_UART3_TX") (class "Default")
      (node (ref "U22") (pin "13") (pinfunction "T1I_13") (pintype "passive"))
    )
    (net (code "45") (name "/MCU_UART4_RX") (class "Default")
      (node (ref "J13") (pin "2") (pinfunction "2_2") (pintype "passive"))
      (node (ref "J17") (pin "1") (pinfunction "1_1") (pintype "passive"))
      (node (ref "J24") (pin "1") (pinfunction "1_1") (pintype "passive"))
    )
    (net (code "46") (name "/MCU_UART4_TX") (class "Default")
      (node (ref "J12") (pin "1") (pinfunction "1_1") (pintype "passive"))
      (node (ref "J16") (pin "1") (pinfunction "1_1") (pintype "passive"))
      (node (ref "J23") (pin "1") (pinfunction "1_1") (pintype "passive"))
    )
    (net (code "47") (name "/MCU_USB_D+") (class "Default")
      (node (ref "L11") (pin "2") (pinfunction "2_2") (pintype "passive"))
    )
    (net (code "48") (name "/MCU_USB_D-") (class "Default")
      (node (ref "L11") (pin "1") (pinfunction "1_1") (pintype "passive"))
    )
    (net (code "49") (name "/PC2TRANS_PC_RX") (class "Default")
      (node (ref "J18") (pin "1") (pinfunction "1_1") (pintype "passive"))
      (node (ref "U23") (pin "15") (pinfunction "R1O_15") (pintype "passive"))
    )
    (net (code "50") (name "/PC2TRANS_PC_TX") (class "Default")
      (node (ref "J21") (pin "2") (pinfunction "2_2") (pintype "passive"))
      (node (ref "U23") (pin "13") (pinfunction "T1I_13") (pintype "passive"))
    )
    (net (code "51") (name "/R1+") (class "Default")
      (node (ref "K1") (pin "9") (pinfunction "9_9") (pintype "passive"))
      (node (ref "P8") (pin "4") (pinfunction "4_4") (pintype "passive"))
    )
    (net (code "52") (name "/R1-") (class "Default")
      (node (ref "P8") (pin "3") (pinfunction "3_3") (pintype "passive"))
      (node (ref "R49") (pin "2") (pinfunction "2_2") (pintype "passive"))
      (node (ref "R51") (pin "2") (pinfunction "2_2") (pintype "passive"))
    )
    (net (code "53") (name "/R2+") (class "Default")
      (node (ref "K2") (pin "9") (pinfunction "9_9") (pintype "passive"))
      (node (ref "P8") (pin "2") (pinfunction "2_2") (pintype "passive"))
    )
    (net (code "54") (name "/R2-") (class "Default")
      (node (ref "P8") (pin "1") (pinfunction "1_1") (pintype "passive"))
      (node (ref "R50") (pin "2") (pinfunction "2_2") (pintype "passive"))
      (node (ref "R53") (pin "2") (pinfunction "2_2") (pintype "passive"))
    )
    (net (code "55") (name "/RELAY1") (class "Default")
      (node (ref "R56") (pin "1") (pinfunction "1_1") (pintype "passive"))
      (node (ref "R69") (pin "2") (pinfunction "2_2") (pintype "passive"))
    )
    (net (code "56") (name "/RELAY2") (class "Default")
      (node (ref "R57") (pin "1") (pinfunction "1_1") (pintype "passive"))
      (node (ref "R70") (pin "2") (pinfunction "2_2") (pintype "passive"))
    )
    (net (code "57") (name "/RS485_DI") (class "Default")
      (node (ref "J23") (pin "2") (pinfunction "2_2") (pintype "passive"))
      (node (ref "U27") (pin "5") (pinfunction "DI_5") (pintype "passive"))
    )
    (net (code "58") (name "/RS485_RES_N") (class "Default")
      (node (ref "D23") (pin "1") (pinfunction "1_1") (pintype "passive"))
      (node (ref "P9") (pin "4") (pinfunction "4_4") (pintype "passive"))
      (node (ref "R76") (pin "2") (pinfunction "2_2") (pintype "passive"))
    )
    (net (code "59") (name "/RS485_RES_P") (class "Default")
      (node (ref "D23") (pin "2") (pinfunction "2_2") (pintype "passive"))
      (node (ref "P9") (pin "3") (pinfunction "3_3") (pintype "passive"))
      (node (ref "R74") (pin "2") (pinfunction "2_2") (pintype "passive"))
    )
    (net (code "60") (name "/RS485_RO") (class "Default")
      (node (ref "C83") (pin "2") (pinfunction "2_2") (pintype "passive"))
      (node (ref "J24") (pin "2") (pinfunction "2_2") (pintype "passive"))
      (node (ref "U27") (pin "4") (pinfunction "RO_4") (pintype "passive"))
    )
    (net (code "61") (name "/RS485_SND_N") (class "Default")
      (node (ref "D22") (pin "2") (pinfunction "2_2") (pintype "passive"))
      (node (ref "P9") (pin "1") (pinfunction "1_1") (pintype "passive"))
      (node (ref "R63") (pin "2") (pinfunction "2_2") (pintype "passive"))
    )
    (net (code "62") (name "/RS485_SND_P") (class "Default")
      (node (ref "D22") (pin "1") (pinfunction "1_1") (pintype "passive"))
      (node (ref "P9") (pin "2") (pinfunction "2_2") (pintype "passive"))
      (node (ref "R64") (pin "2") (pinfunction "2_2") (pintype "passive"))
    )
    (net (code "63") (name "/SCL_MCU") (class "Default")
      (node (ref "P4") (pin "3") (pinfunction "3_3") (pintype "passive"))
      (node (ref "R46") (pin "1") (pinfunction "1_1") (pintype "passive"))
    )
    (net (code "64") (name "/SDA_MCU") (class "Default")
      (node (ref "P4") (pin "1") (pinfunction "1_1") (pintype "passive"))
      (node (ref "R45") (pin "1") (pinfunction "1_1") (pintype "passive"))
    )
    (net (code "65") (name "/SER1_RS_RX") (class "Default")
      (node (ref "P7") (pin "1") (pinfunction "1_1") (pintype "passive"))
      (node (ref "U23") (pin "9") (pinfunction "R2I_9") (pintype "passive"))
    )
    (net (code "66") (name "/SER1_RS_TX") (class "Default")
      (node (ref "P7") (pin "3") (pinfunction "3_3") (pintype "passive"))
      (node (ref "U23") (pin "8") (pinfunction "T2O_8") (pintype "passive"))
    )
    (net (code "67") (name "/TRANS2LCD_RX") (class "Default")
      (node (ref "J20") (pin "2") (pinfunction "2_2") (pintype "passive"))
      (node (ref "P5") (pin "6") (pinfunction "6_6") (pintype "passive"))
    )
    (net (code "68") (name "/TRANS2LCD_TX") (class "Default")
      (node (ref "J19") (pin "2") (pinfunction "2_2") (pintype "passive"))
      (node (ref "P5") (pin "5") (pinfunction "5_5") (pintype "passive"))
    )
    (net (code "69") (name "/TRANS2TRANS_RX") (class "Default")
      (node (ref "J15") (pin "2") (pinfunction "2_2") (pintype "passive"))
      (node (ref "P6") (pin "1") (pinfunction "1_1") (pintype "passive"))
      (node (ref "U23") (pin "17") (pinfunction "T1O_17") (pintype "passive"))
    )
    (net (code "70") (name "/TRANS2TRANS_TX") (class "Default")
      (node (ref "J14") (pin "2") (pinfunction "2_2") (pintype "passive"))
      (node (ref "P6") (pin "3") (pinfunction "3_3") (pintype "passive"))
      (node (ref "U23") (pin "16") (pinfunction "R1I_16") (pintype "passive"))
    )
    (net (code "71") (name "/VBUS") (class "Default")
      (node (ref "D19") (pin "1") (pinfunction "1_1") (pintype "passive"))
    )
    (net (code "72") (name "GND") (class "Default")
      (node (ref "C64") (pin "2") (pinfunction "2_2") (pintype "passive"))
      (node (ref "C65") (pin "1") (pinfunction "1_1") (pintype "passive"))
      (node (ref "C66") (pin "1") (pinfunction "1_1") (pintype "passive"))
      (node (ref "C67") (pin "2") (pinfunction "2_2") (pintype "passive"))
      (node (ref "C69") (pin "2") (pinfunction "2_2") (pintype "passive"))
      (node (ref "C70") (pin "1") (pinfunction "1_1") (pintype "passive"))
      (node (ref "C72") (pin "1") (pinfunction "1_1") (pintype "passive"))
      (node (ref "C74") (pin "1") (pinfunction "1_1") (pintype "passive"))
      (node (ref "C75") (pin "2") (pinfunction "2_2") (pintype "passive"))
      (node (ref "C77") (pin "2") (pinfunction "2_2") (pintype "passive"))
      (node (ref "C79") (pin "1") (pinfunction "1_1") (pintype "passive"))
      (node (ref "C80") (pin "1") (pinfunction "1_1") (pintype "passive"))
      (node (ref "C82") (pin "1") (pinfunction "1_1") (pintype "passive"))
      (node (ref "C83") (pin "1") (pinfunction "1_1") (pintype "passive"))
      (node (ref "D18") (pin "3") (pinfunction "3_3") (pintype "passive"))
      (node (ref "D22") (pin "3") (pinfunction "3_3") (pintype "passive"))
      (node (ref "D24") (pin "2") (pinfunction "K_2") (pintype "passive"))
      (node (ref "D25") (pin "2") (pinfunction "K_2") (pintype "passive"))
      (node (ref "D28") (pin "2") (pinfunction "K_2") (pintype "passive"))
      (node (ref "D29") (pin "2") (pinfunction "K_2") (pintype "passive"))
      (node (ref "J26") (pin "2") (pinfunction "2_2") (pintype "passive"))
      (node (ref "J27") (pin "4") (pinfunction "GND_4") (pintype "passive"))
      (node (ref "J28") (pin "14") (pinfunction "14_14") (pintype "passive"))
      (node (ref "J28") (pin "19") (pinfunction "19_19") (pintype "passive"))
      (node (ref "J28") (pin "20") (pinfunction "20_20") (pintype "passive"))
      (node (ref "J28") (pin "21") (pinfunction "21_21") (pintype "passive"))
      (node (ref "J28") (pin "22") (pinfunction "22_22") (pintype "passive"))
      (node (ref "J28") (pin "5") (pinfunction "5_5") (pintype "passive"))
      (node (ref "J31") (pin "14") (pinfunction "14_14") (pintype "passive"))
      (node (ref "J31") (pin "19") (pinfunction "19_19") (pintype "passive"))
      (node (ref "J31") (pin "20") (pinfunction "20_20") (pintype "passive"))
      (node (ref "J31") (pin "21") (pinfunction "21_21") (pintype "passive"))
      (node (ref "J31") (pin "22") (pinfunction "22_22") (pintype "passive"))
      (node (ref "J31") (pin "5") (pinfunction "5_5") (pintype "passive"))
      (node (ref "P3") (pin "2") (pinfunction "2_2") (pintype "passive"))
      (node (ref "P4") (pin "2") (pinfunction "2_2") (pintype "passive"))
      (node (ref "P5") (pin "3") (pinfunction "3_3") (pintype "passive"))
      (node (ref "P5") (pin "4") (pinfunction "4_4") (pintype "passive"))
      (node (ref "P6") (pin "2") (pinfunction "2_2") (pintype "passive"))
      (node (ref "P7") (pin "2") (pinfunction "2_2") (pintype "passive"))
      (node (ref "P9") (pin "5") (pinfunction "5_5") (pintype "passive"))
      (node (ref "Q7") (pin "2") (pinfunction "S_2") (pintype "passive"))
      (node (ref "Q8") (pin "2") (pinfunction "E_2") (pintype "passive"))
      (node (ref "Q9") (pin "2") (pinfunction "E_2") (pintype "passive"))
      (node (ref "R43") (pin "2") (pinfunction "2_2") (pintype "passive"))
      (node (ref "R47") (pin "1") (pinfunction "1_1") (pintype "passive"))
      (node (ref "U18") (pin "2") (pinfunction "GND_2") (pintype "power_in"))
      (node (ref "U19") (pin "2") (pinfunction "GND_2") (pintype "power_in"))
      (node (ref "U20") (pin "1") (pinfunction "/EN_1") (pintype "passive"))
      (node (ref "U20") (pin "18") (pinfunction "GND_18") (pintype "passive"))
      (node (ref "U21") (pin "1") (pinfunction "-Vin_1") (pintype "passive"))
      (node (ref "U22") (pin "1") (pinfunction "/EN_1") (pintype "passive"))
      (node (ref "U22") (pin "18") (pinfunction "GND_18") (pintype "passive"))
      (node (ref "U23") (pin "1") (pinfunction "/EN_1") (pintype "passive"))
      (node (ref "U23") (pin "18") (pinfunction "GND_18") (pintype "passive"))
      (node (ref "U24") (pin "3") (pinfunction "E_3") (pintype "passive"))
      (node (ref "U25") (pin "3") (pinfunction "E_3") (pintype "passive"))
      (node (ref "U26") (pin "2") (pinfunction "K_2") (pintype "passive"))
      (node (ref "U27") (pin "6") (pinfunction "Gnd_6") (pintype "passive"))
      (node (ref "U28") (pin "2") (pinfunction "K_2") (pintype "passive"))
      (node (ref "U29") (pin "3") (pinfunction "E_3") (pintype "passive"))
    )
    (net (code "73") (name "GND_EXT") (class "Default")
      (node (ref "P8") (pin "6") (pinfunction "6_6") (pintype "passive"))
      (node (ref "U25") (pin "2") (pinfunction "K_2") (pintype "passive"))
      (node (ref "U26") (pin "3") (pinfunction "E_3") (pintype "passive"))
      (node (ref "U28") (pin "3") (pinfunction "E_3") (pintype "passive"))
      (node (ref "U29") (pin "2") (pinfunction "K_2") (pintype "passive"))
    )
    (net (code "74") (name "Net-(D20-Pad2)") (class "Default")
      (node (ref "D20") (pin "2") (pinfunction "2_2") (pintype "passive"))
      (node (ref "K1") (pin "12") (pinfunction "12_12") (pintype "passive"))
      (node (ref "R52") (pin "2") (pinfunction "2_2") (pintype "passive"))
    )
    (net (code "75") (name "Net-(D21-Pad2)") (class "Default")
      (node (ref "D21") (pin "2") (pinfunction "2_2") (pintype "passive"))
      (node (ref "K2") (pin "12") (pinfunction "12_12") (pintype "passive"))
      (node (ref "R54") (pin "2") (pinfunction "2_2") (pintype "passive"))
    )
    (net (code "76") (name "Net-(D24-A)") (class "Default")
      (node (ref "D24") (pin "1") (pinfunction "A_1") (pintype "passive"))
      (node (ref "R65") (pin "1") (pinfunction "1_1") (pintype "passive"))
    )
    (net (code "77") (name "Net-(D25-A)") (class "Default")
      (node (ref "D25") (pin "1") (pinfunction "A_1") (pintype "passive"))
      (node (ref "R66") (pin "1") (pinfunction "1_1") (pintype "passive"))
    )
    (net (code "78") (name "Net-(D26-A)") (class "Default")
      (node (ref "D26") (pin "1") (pinfunction "A_1") (pintype "passive"))
      (node (ref "R67") (pin "1") (pinfunction "1_1") (pintype "passive"))
    )
    (net (code "79") (name "Net-(D27-A)") (class "Default")
      (node (ref "D27") (pin "1") (pinfunction "A_1") (pintype "passive"))
      (node (ref "R68") (pin "1") (pinfunction "1_1") (pintype "passive"))
    )
    (net (code "80") (name "Net-(D28-A)") (class "Default")
      (node (ref "D28") (pin "1") (pinfunction "A_1") (pintype "passive"))
      (node (ref "R69") (pin "1") (pinfunction "1_1") (pintype "passive"))
    )
    (net (code "81") (name "Net-(D29-A)") (class "Default")
      (node (ref "D29") (pin "1") (pinfunction "A_1") (pintype "passive"))
      (node (ref "R70") (pin "1") (pinfunction "1_1") (pintype "passive"))
    )
    (net (code "82") (name "Net-(J27-VBUS)") (class "Default")
      (node (ref "C67") (pin "1") (pinfunction "1_1") (pintype "passive"))
      (node (ref "D19") (pin "2") (pinfunction "2_2") (pintype "passive"))
      (node (ref "J27") (pin "1") (pinfunction "VBUS_1") (pintype "passive"))
    )
    (net (code "83") (name "Net-(J30-Pad3)") (class "Default")
      (node (ref "J30") (pin "3") (pinfunction "3_3") (pintype "passive"))
      (node (ref "J33") (pin "3") (pinfunction "3_3") (pintype "passive"))
      (node (ref "J34") (pin "3") (pinfunction "3_3") (pintype "passive"))
    )
    (net (code "84") (name "Net-(J34-Pad2)") (class "Default")
      (node (ref "J34") (pin "2") (pinfunction "2_2") (pintype "passive"))
      (node (ref "R55") (pin "1") (pinfunction "1_1") (pintype "passive"))
    )
    (net (code "85") (name "Net-(K1-Pad8)") (class "Default")
      (node (ref "K1") (pin "8") (pinfunction "8_8") (pintype "passive"))
      (node (ref "R49") (pin "1") (pinfunction "1_1") (pintype "passive"))
    )
    (net (code "86") (name "Net-(K1-Pad10)") (class "Default")
      (node (ref "K1") (pin "10") (pinfunction "10_10") (pintype "passive"))
      (node (ref "R51") (pin "1") (pinfunction "1_1") (pintype "passive"))
    )
    (net (code "87") (name "Net-(K2-Pad8)") (class "Default")
      (node (ref "K2") (pin "8") (pinfunction "8_8") (pintype "passive"))
      (node (ref "R50") (pin "1") (pinfunction "1_1") (pintype "passive"))
    )
    (net (code "88") (name "Net-(K2-Pad10)") (class "Default")
      (node (ref "K2") (pin "10") (pinfunction "10_10") (pintype "passive"))
      (node (ref "R53") (pin "1") (pinfunction "1_1") (pintype "passive"))
    )
    (net (code "89") (name "Net-(LS2--V)") (class "Default")
      (node (ref "LS2") (pin "2") (pinfunction "-V_2") (pintype "passive"))
      (node (ref "Q7") (pin "3") (pinfunction "D_3") (pintype "passive"))
    )
    (net (code "90") (name "Net-(Q8-B)") (class "Default")
      (node (ref "Q8") (pin "1") (pinfunction "B_1") (pintype "passive"))
      (node (ref "R56") (pin "2") (pinfunction "2_2") (pintype "passive"))
    )
    (net (code "91") (name "Net-(Q8-C)") (class "Default")
      (node (ref "Q8") (pin "3") (pinfunction "C_3") (pintype "passive"))
      (node (ref "R52") (pin "1") (pinfunction "1_1") (pintype "passive"))
    )
    (net (code "92") (name "Net-(Q9-B)") (class "Default")
      (node (ref "Q9") (pin "1") (pinfunction "B_1") (pintype "passive"))
      (node (ref "R57") (pin "2") (pinfunction "2_2") (pintype "passive"))
    )
    (net (code "93") (name "Net-(Q9-C)") (class "Default")
      (node (ref "Q9") (pin "3") (pinfunction "C_3") (pintype "passive"))
      (node (ref "R54") (pin "1") (pinfunction "1_1") (pintype "passive"))
    )
    (net (code "94") (name "Net-(U18-S)") (class "Default")
      (node (ref "C64") (pin "1") (pinfunction "1_1") (pintype "passive"))
      (node (ref "R42") (pin "1") (pinfunction "1_1") (pintype "passive"))
      (node (ref "R43") (pin "1") (pinfunction "1_1") (pintype "passive"))
      (node (ref "U18") (pin "8") (pinfunction "S_8") (pintype "passive"))
    )
    (net (code "95") (name "Net-(U20-C1+)") (class "Default")
      (node (ref "C68") (pin "2") (pinfunction "2_2") (pintype "passive"))
      (node (ref "U20") (pin "2") (pinfunction "C1+_2") (pintype "passive"))
    )
    (net (code "96") (name "Net-(U20-C1-)") (class "Default")
      (node (ref "C68") (pin "1") (pinfunction "1_1") (pintype "passive"))
      (node (ref "U20") (pin "4") (pinfunction "C1-_4") (pintype "passive"))
    )
    (net (code "97") (name "Net-(U20-C2+)") (class "Default")
      (node (ref "C71") (pin "2") (pinfunction "2_2") (pintype "passive"))
      (node (ref "U20") (pin "5") (pinfunction "C2+_5") (pintype "passive"))
    )
    (net (code "98") (name "Net-(U20-C2-)") (class "Default")
      (node (ref "C71") (pin "1") (pinfunction "1_1") (pintype "passive"))
      (node (ref "U20") (pin "6") (pinfunction "C2-_6") (pintype "passive"))
    )
    (net (code "99") (name "Net-(U20-V+)") (class "Default")
      (node (ref "C70") (pin "2") (pinfunction "2_2") (pintype "passive"))
      (node (ref "U20") (pin "3") (pinfunction "V+_3") (pintype "passive"))
    )
    (net (code "100") (name "Net-(U20-V-)") (class "Default")
      (node (ref "C72") (pin "2") (pinfunction "2_2") (pintype "passive"))
      (node (ref "U20") (pin "7") (pinfunction "V-_7") (pintype "passive"))
    )
    (net (code "101") (name "Net-(U21-+Vout)") (class "Default")
      (node (ref "J32") (pin "1") (pinfunction "1_1") (pintype "passive"))
      (node (ref "U21") (pin "4") (pinfunction "+Vout_4") (pintype "passive"))
    )
    (net (code "102") (name "Net-(U21--Vout)") (class "Default")
      (node (ref "J29") (pin "2") (pinfunction "2_2") (pintype "passive"))
      (node (ref "J34") (pin "1") (pinfunction "1_1") (pintype "passive"))
      (node (ref "U21") (pin "3") (pinfunction "-Vout_3") (pintype "passive"))
    )
    (net (code "103") (name "Net-(U22-C1+)") (class "Default")
      (node (ref "C73") (pin "1") (pinfunction "1_1") (pintype "passive"))
      (node (ref "U22") (pin "2") (pinfunction "C1+_2") (pintype "passive"))
    )
    (net (code "104") (name "Net-(U22-C1-)") (class "Default")
      (node (ref "C73") (pin "2") (pinfunction "2_2") (pintype "passive"))
      (node (ref "U22") (pin "4") (pinfunction "C1-_4") (pintype "passive"))
    )
    (net (code "105") (name "Net-(U22-C2+)") (class "Default")
      (node (ref "C76") (pin "1") (pinfunction "1_1") (pintype "passive"))
      (node (ref "U22") (pin "5") (pinfunction "C2+_5") (pintype "passive"))
    )
    (net (code "106") (name "Net-(U22-C2-)") (class "Default")
      (node (ref "C76") (pin "2") (pinfunction "2_2") (pintype "passive"))
      (node (ref "U22") (pin "6") (pinfunction "C2-_6") (pintype "passive"))
    )
    (net (code "107") (name "Net-(U22-V+)") (class "Default")
      (node (ref "C75") (pin "1") (pinfunction "1_1") (pintype "passive"))
      (node (ref "U22") (pin "3") (pinfunction "V+_3") (pintype "passive"))
    )
    (net (code "108") (name "Net-(U22-V-)") (class "Default")
      (node (ref "C77") (pin "1") (pinfunction "1_1") (pintype "passive"))
      (node (ref "U22") (pin "7") (pinfunction "V-_7") (pintype "passive"))
    )
    (net (code "109") (name "Net-(U23-C1+)") (class "Default")
      (node (ref "C78") (pin "1") (pinfunction "1_1") (pintype "passive"))
      (node (ref "U23") (pin "2") (pinfunction "C1+_2") (pintype "passive"))
    )
    (net (code "110") (name "Net-(U23-C1-)") (class "Default")
      (node (ref "C78") (pin "2") (pinfunction "2_2") (pintype "passive"))
      (node (ref "U23") (pin "4") (pinfunction "C1-_4") (pintype "passive"))
    )
    (net (code "111") (name "Net-(U23-C2+)") (class "Default")
      (node (ref "C81") (pin "1") (pinfunction "1_1") (pintype "passive"))
      (node (ref "U23") (pin "5") (pinfunction "C2+_5") (pintype "passive"))
    )
    (net (code "112") (name "Net-(U23-C2-)") (class "Default")
      (node (ref "C81") (pin "2") (pinfunction "2_2") (pintype "passive"))
      (node (ref "U23") (pin "6") (pinfunction "C2-_6") (pintype "passive"))
    )
    (net (code "113") (name "Net-(U23-V+)") (class "Default")
      (node (ref "C80") (pin "2") (pinfunction "2_2") (pintype "passive"))
      (node (ref "U23") (pin "3") (pinfunction "V+_3") (pintype "passive"))
    )
    (net (code "114") (name "Net-(U23-V-)") (class "Default")
      (node (ref "C82") (pin "2") (pinfunction "2_2") (pintype "passive"))
      (node (ref "U23") (pin "7") (pinfunction "V-_7") (pintype "passive"))
    )
    (net (code "115") (name "Net-(U24-A)") (class "Default")
      (node (ref "J30") (pin "1") (pinfunction "1_1") (pintype "passive"))
      (node (ref "J32") (pin "2") (pinfunction "2_2") (pintype "passive"))
      (node (ref "J33") (pin "1") (pinfunction "1_1") (pintype "passive"))
      (node (ref "U24") (pin "1") (pinfunction "A_1") (pintype "passive"))
    )
    (net (code "116") (name "Net-(U24-K)") (class "Default")
      (node (ref "R55") (pin "2") (pinfunction "2_2") (pintype "passive"))
      (node (ref "U24") (pin "2") (pinfunction "K_2") (pintype "passive"))
    )
    (net (code "117") (name "Net-(U25-A)") (class "Default")
      (node (ref "R61") (pin "2") (pinfunction "2_2") (pintype "passive"))
      (node (ref "U25") (pin "1") (pinfunction "A_1") (pintype "passive"))
    )
    (net (code "118") (name "Net-(U26-A)") (class "Default")
      (node (ref "R62") (pin "2") (pinfunction "2_2") (pintype "passive"))
      (node (ref "U26") (pin "1") (pinfunction "A_1") (pintype "passive"))
    )
    (net (code "119") (name "Net-(U27-A)") (class "Default")
      (node (ref "R60") (pin "2") (pinfunction "2_2") (pintype "passive"))
      (node (ref "R74") (pin "1") (pinfunction "1_1") (pintype "passive"))
      (node (ref "U27") (pin "2") (pinfunction "A_2") (pintype "passive"))
    )
    (net (code "120") (name "Net-(U27-B)") (class "Default")
      (node (ref "R60") (pin "1") (pinfunction "1_1") (pintype "passive"))
      (node (ref "R76") (pin "1") (pinfunction "1_1") (pintype "passive"))
      (node (ref "U27") (pin "1") (pinfunction "B_1") (pintype "passive"))
    )
    (net (code "121") (name "Net-(U27-Y)") (class "Default")
      (node (ref "R64") (pin "1") (pinfunction "1_1") (pintype "passive"))
      (node (ref "U27") (pin "7") (pinfunction "Y_7") (pintype "passive"))
    )
    (net (code "122") (name "Net-(U27-Z)") (class "Default")
      (node (ref "R63") (pin "1") (pinfunction "1_1") (pintype "passive"))
      (node (ref "U27") (pin "8") (pinfunction "Z_8") (pintype "passive"))
    )
    (net (code "123") (name "Net-(U28-A)") (class "Default")
      (node (ref "R73") (pin "2") (pinfunction "2_2") (pintype "passive"))
      (node (ref "U28") (pin "1") (pinfunction "A_1") (pintype "passive"))
    )
    (net (code "124") (name "Net-(U29-A)") (class "Default")
      (node (ref "R75") (pin "2") (pinfunction "2_2") (pintype "passive"))
      (node (ref "U29") (pin "1") (pinfunction "A_1") (pintype "passive"))
    )
    (net (code "125") (name "VCC_EXT") (class "Default")
      (node (ref "P8") (pin "10") (pinfunction "10_10") (pintype "passive"))
      (node (ref "R58") (pin "2") (pinfunction "2_2") (pintype "passive"))
      (node (ref "R71") (pin "2") (pinfunction "2_2") (pintype "passive"))
    )
    (net (code "126") (name "unconnected-(D23-Pad3)") (class "Default")
      (node (ref "D23") (pin "3") (pinfunction "3_3") (pintype "passive"))
    )
    (net (code "127") (name "unconnected-(J27-SHLD1-Pad5)") (class "Default")
      (node (ref "J27") (pin "5") (pinfunction "SHLD1_5") (pintype "passive+no_connect"))
    )
    (net (code "128") (name "unconnected-(J27-SHLD2-Pad6)") (class "Default")
      (node (ref "J27") (pin "6") (pinfunction "SHLD2_6") (pintype "passive+no_connect"))
    )
    (net (code "129") (name "unconnected-(J28-Pad1)") (class "Default")
      (node (ref "J28") (pin "1") (pinfunction "1_1") (pintype "passive"))
    )
    (net (code "130") (name "unconnected-(J28-Pad4)") (class "Default")
      (node (ref "J28") (pin "4") (pinfunction "4_4") (pintype "passive"))
    )
    (net (code "131") (name "unconnected-(J28-Pad6)") (class "Default")
      (node (ref "J28") (pin "6") (pinfunction "6_6") (pintype "passive"))
    )
    (net (code "132") (name "unconnected-(J28-Pad7)") (class "Default")
      (node (ref "J28") (pin "7") (pinfunction "7_7") (pintype "passive"))
    )
    (net (code "133") (name "unconnected-(J28-Pad8)") (class "Default")
      (node (ref "J28") (pin "8") (pinfunction "8_8") (pintype "passive"))
    )
    (net (code "134") (name "unconnected-(J28-Pad9)") (class "Default")
      (node (ref "J28") (pin "9") (pinfunction "9_9") (pintype "passive"))
    )
    (net (code "135") (name "unconnected-(J28-Pad10)") (class "Default")
      (node (ref "J28") (pin "10") (pinfunction "10_10") (pintype "passive"))
    )
    (net (code "136") (name "unconnected-(J28-Pad13)") (class "Default")
      (node (ref "J28") (pin "13") (pinfunction "13_13") (pintype "passive"))
    )
    (net (code "137") (name "unconnected-(J28-Pad15)") (class "Default")
      (node (ref "J28") (pin "15") (pinfunction "15_15") (pintype "passive"))
    )
    (net (code "138") (name "unconnected-(J28-Pad16)") (class "Default")
      (node (ref "J28") (pin "16") (pinfunction "16_16") (pintype "passive"))
    )
    (net (code "139") (name "unconnected-(J28-Pad17)") (class "Default")
      (node (ref "J28") (pin "17") (pinfunction "17_17") (pintype "passive"))
    )
    (net (code "140") (name "unconnected-(J28-Pad18)") (class "Default")
      (node (ref "J28") (pin "18") (pinfunction "18_18") (pintype "passive"))
    )
    (net (code "141") (name "unconnected-(J29-Pad1)") (class "Default")
      (node (ref "J29") (pin "1") (pinfunction "1_1") (pintype "passive"))
    )
    (net (code "142") (name "unconnected-(J31-Pad1)") (class "Default")
      (node (ref "J31") (pin "1") (pinfunction "1_1") (pintype "passive"))
    )
    (net (code "143") (name "unconnected-(J31-Pad4)") (class "Default")
      (node (ref "J31") (pin "4") (pinfunction "4_4") (pintype "passive"))
    )
    (net (code "144") (name "unconnected-(J31-Pad6)") (class "Default")
      (node (ref "J31") (pin "6") (pinfunction "6_6") (pintype "passive"))
    )
    (net (code "145") (name "unconnected-(J31-Pad7)") (class "Default")
      (node (ref "J31") (pin "7") (pinfunction "7_7") (pintype "passive"))
    )
    (net (code "146") (name "unconnected-(J31-Pad8)") (class "Default")
      (node (ref "J31") (pin "8") (pinfunction "8_8") (pintype "passive"))
    )
    (net (code "147") (name "unconnected-(J31-Pad9)") (class "Default")
      (node (ref "J31") (pin "9") (pinfunction "9_9") (pintype "passive"))
    )
    (net (code "148") (name "unconnected-(J31-Pad10)") (class "Default")
      (node (ref "J31") (pin "10") (pinfunction "10_10") (pintype "passive"))
    )
    (net (code "149") (name "unconnected-(J31-Pad13)") (class "Default")
      (node (ref "J31") (pin "13") (pinfunction "13_13") (pintype "passive"))
    )
    (net (code "150") (name "unconnected-(J31-Pad15)") (class "Default")
      (node (ref "J31") (pin "15") (pinfunction "15_15") (pintype "passive"))
    )
    (net (code "151") (name "unconnected-(J31-Pad16)") (class "Default")
      (node (ref "J31") (pin "16") (pinfunction "16_16") (pintype "passive"))
    )
    (net (code "152") (name "unconnected-(J31-Pad17)") (class "Default")
      (node (ref "J31") (pin "17") (pinfunction "17_17") (pintype "passive"))
    )
    (net (code "153") (name "unconnected-(J31-Pad18)") (class "Default")
      (node (ref "J31") (pin "18") (pinfunction "18_18") (pintype "passive"))
    )
    (net (code "154") (name "unconnected-(K1-Pad3)") (class "Default")
      (node (ref "K1") (pin "3") (pinfunction "3_3") (pintype "passive"))
    )
    (net (code "155") (name "unconnected-(K1-Pad4)") (class "Default")
      (node (ref "K1") (pin "4") (pinfunction "4_4") (pintype "passive"))
    )
    (net (code "156") (name "unconnected-(K1-Pad5)") (class "Default")
      (node (ref "K1") (pin "5") (pinfunction "5_5") (pintype "passive"))
    )
    (net (code "157") (name "unconnected-(K2-Pad3)") (class "Default")
      (node (ref "K2") (pin "3") (pinfunction "3_3") (pintype "passive"))
    )
    (net (code "158") (name "unconnected-(K2-Pad4)") (class "Default")
      (node (ref "K2") (pin "4") (pinfunction "4_4") (pintype "passive"))
    )
    (net (code "159") (name "unconnected-(K2-Pad5)") (class "Default")
      (node (ref "K2") (pin "5") (pinfunction "5_5") (pintype "passive"))
    )
    (net (code "160") (name "unconnected-(P5-Pad7)") (class "Default")
      (node (ref "P5") (pin "7") (pinfunction "7_7") (pintype "passive+no_connect"))
    )
    (net (code "161") (name "unconnected-(U18-VREF-Pad5)") (class "Default")
      (node (ref "U18") (pin "5") (pinfunction "VREF_5") (pintype "power_in+no_connect"))
    )
    (net (code "162") (name "unconnected-(U19-NC-Pad3)") (class "Default")
      (node (ref "U19") (pin "3") (pinfunction "NC_3") (pintype "passive+no_connect"))
    )
    (net (code "163") (name "unconnected-(U19-NC-Pad6)") (class "Default")
      (node (ref "U19") (pin "6") (pinfunction "NC_6") (pintype "passive+no_connect"))
    )
    (net (code "164") (name "unconnected-(U20-NC-Pad11)") (class "Default")
      (node (ref "U20") (pin "11") (pinfunction "NC_11") (pintype "passive+no_connect"))
    )
    (net (code "165") (name "unconnected-(U20-NC-Pad14)") (class "Default")
      (node (ref "U20") (pin "14") (pinfunction "NC_14") (pintype "passive+no_connect"))
    )
    (net (code "166") (name "unconnected-(U22-NC-Pad11)") (class "Default")
      (node (ref "U22") (pin "11") (pinfunction "NC_11") (pintype "passive+no_connect"))
    )
    (net (code "167") (name "unconnected-(U22-NC-Pad14)") (class "Default")
      (node (ref "U22") (pin "14") (pinfunction "NC_14") (pintype "passive+no_connect"))
    )
    (net (code "168") (name "unconnected-(U23-NC-Pad11)") (class "Default")
      (node (ref "U23") (pin "11") (pinfunction "NC_11") (pintype "passive+no_connect"))
    )
    (net (code "169") (name "unconnected-(U23-NC-Pad14)") (class "Default")
      (node (ref "U23") (pin "14") (pinfunction "NC_14") (pintype "passive+no_connect"))
    )
  )
)
